# qdr0_1.net
KiCad netlist of a schematic drawn in Altium Designer
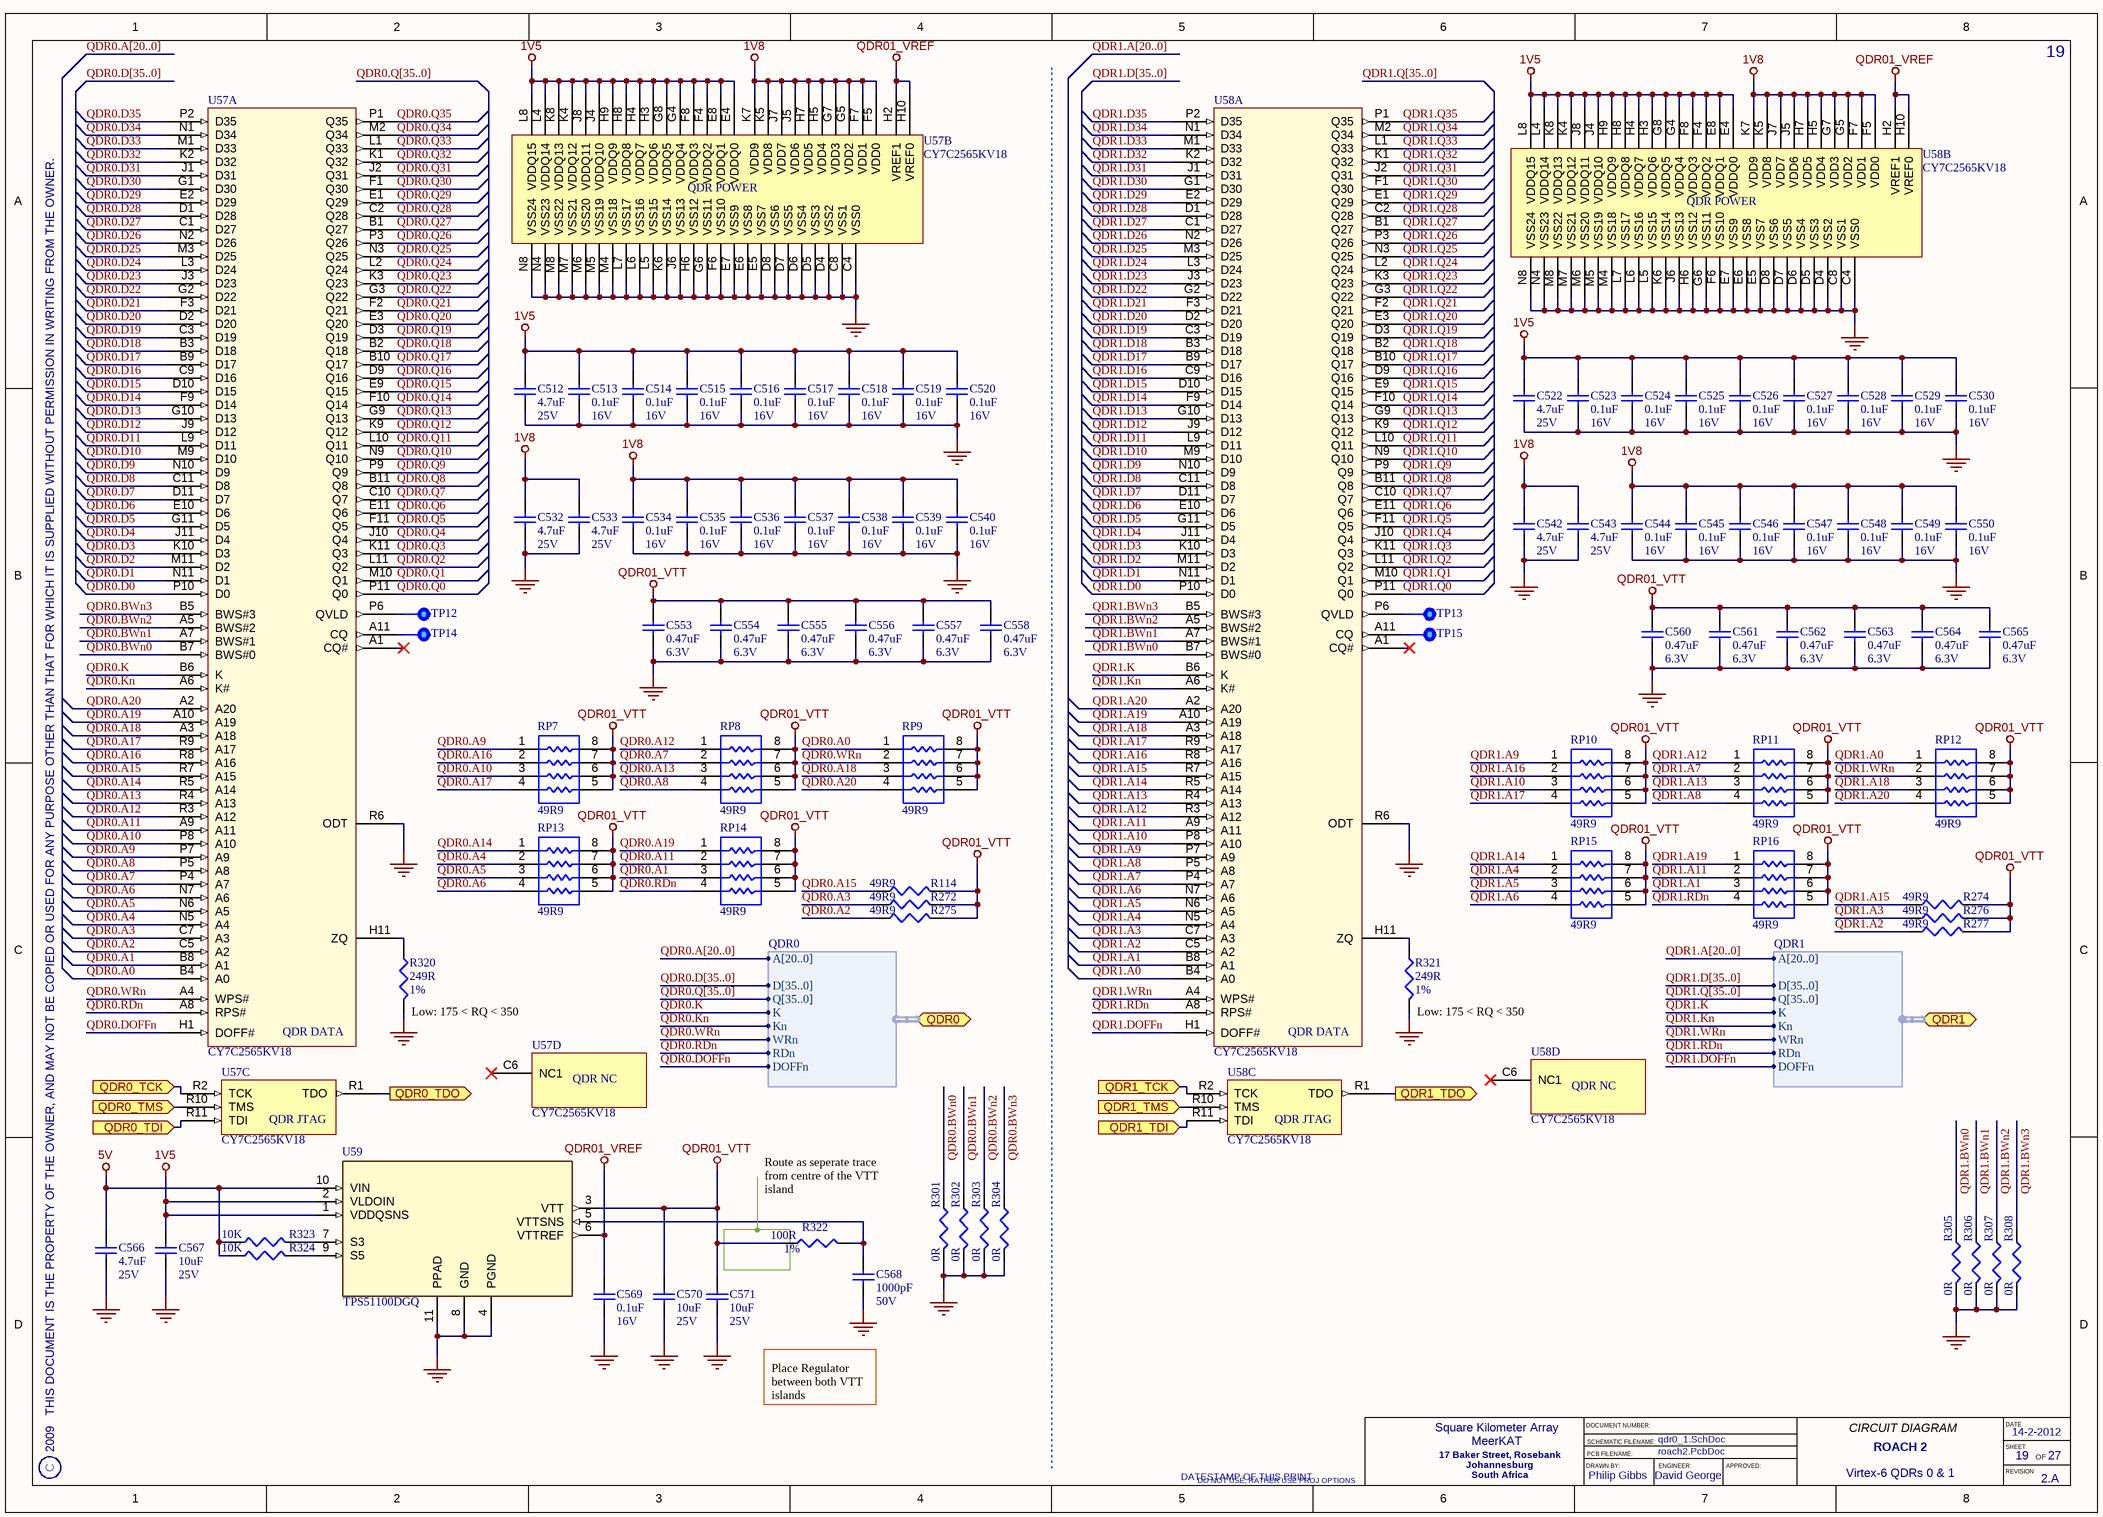
[diagram p0: qdr0_1.SchDoc]

(export (version "E")
  (design (tool "Eeschema 10.0.6"))
  (components
    (comp (ref "C512")
      (value "4.7uF")
      (footprint "CAPC2012X127L")
      (description "4.7uF, Ceramic Capacitor")
      (fields
        (field (name "RATING") "25V")
        (field (name "MANUFACTURER") "MURATA")
        (field (name "PARTNUM") "GRM21BR61E475KA12K")
      )
      (libsource (lib "altium_db") (part "CapStd"))
    )
    (comp (ref "C513")
      (value "0.1uF")
      (footprint "CAPC1005X60L")
      (description "0.1uF, Ceramic Capacitor")
      (fields
        (field (name "RATING") "16V")
        (field (name "MANUFACTURER") "VENKEL")
        (field (name "PARTNUM") "C0402X7R160-104KN")
      )
      (libsource (lib "altium_db") (part "CapStd"))
    )
    (comp (ref "C514")
      (value "0.1uF")
      (footprint "CAPC1005X60L")
      (description "0.1uF, Ceramic Capacitor")
      (fields
        (field (name "RATING") "16V")
        (field (name "MANUFACTURER") "VENKEL")
        (field (name "PARTNUM") "C0402X7R160-104KN")
      )
      (libsource (lib "altium_db") (part "CapStd"))
    )
    (comp (ref "C515")
      (value "0.1uF")
      (footprint "CAPC1005X60L")
      (description "0.1uF, Ceramic Capacitor")
      (fields
        (field (name "RATING") "16V")
        (field (name "MANUFACTURER") "VENKEL")
        (field (name "PARTNUM") "C0402X7R160-104KN")
      )
      (libsource (lib "altium_db") (part "CapStd"))
    )
    (comp (ref "C516")
      (value "0.1uF")
      (footprint "CAPC1005X60L")
      (description "0.1uF, Ceramic Capacitor")
      (fields
        (field (name "RATING") "16V")
        (field (name "MANUFACTURER") "VENKEL")
        (field (name "PARTNUM") "C0402X7R160-104KN")
      )
      (libsource (lib "altium_db") (part "CapStd"))
    )
    (comp (ref "C517")
      (value "0.1uF")
      (footprint "CAPC1005X60L")
      (description "0.1uF, Ceramic Capacitor")
      (fields
        (field (name "RATING") "16V")
        (field (name "MANUFACTURER") "VENKEL")
        (field (name "PARTNUM") "C0402X7R160-104KN")
      )
      (libsource (lib "altium_db") (part "CapStd"))
    )
    (comp (ref "C518")
      (value "0.1uF")
      (footprint "CAPC1005X60L")
      (description "0.1uF, Ceramic Capacitor")
      (fields
        (field (name "RATING") "16V")
        (field (name "MANUFACTURER") "VENKEL")
        (field (name "PARTNUM") "C0402X7R160-104KN")
      )
      (libsource (lib "altium_db") (part "CapStd"))
    )
    (comp (ref "C519")
      (value "0.1uF")
      (footprint "CAPC1005X60L")
      (description "0.1uF, Ceramic Capacitor")
      (fields
        (field (name "RATING") "16V")
        (field (name "MANUFACTURER") "VENKEL")
        (field (name "PARTNUM") "C0402X7R160-104KN")
      )
      (libsource (lib "altium_db") (part "CapStd"))
    )
    (comp (ref "C520")
      (value "0.1uF")
      (footprint "CAPC1005X60L")
      (description "0.1uF, Ceramic Capacitor")
      (fields
        (field (name "RATING") "16V")
        (field (name "MANUFACTURER") "VENKEL")
        (field (name "PARTNUM") "C0402X7R160-104KN")
      )
      (libsource (lib "altium_db") (part "CapStd"))
    )
    (comp (ref "C522")
      (value "4.7uF")
      (footprint "CAPC2012X127L")
      (description "4.7uF, Ceramic Capacitor")
      (fields
        (field (name "RATING") "25V")
        (field (name "MANUFACTURER") "MURATA")
        (field (name "PARTNUM") "GRM21BR61E475KA12K")
      )
      (libsource (lib "altium_db") (part "CapStd"))
    )
    (comp (ref "C523")
      (value "0.1uF")
      (footprint "CAPC1005X60L")
      (description "0.1uF, Ceramic Capacitor")
      (fields
        (field (name "RATING") "16V")
        (field (name "MANUFACTURER") "VENKEL")
        (field (name "PARTNUM") "C0402X7R160-104KN")
      )
      (libsource (lib "altium_db") (part "CapStd"))
    )
    (comp (ref "C524")
      (value "0.1uF")
      (footprint "CAPC1005X60L")
      (description "0.1uF, Ceramic Capacitor")
      (fields
        (field (name "RATING") "16V")
        (field (name "MANUFACTURER") "VENKEL")
        (field (name "PARTNUM") "C0402X7R160-104KN")
      )
      (libsource (lib "altium_db") (part "CapStd"))
    )
    (comp (ref "C525")
      (value "0.1uF")
      (footprint "CAPC1005X60L")
      (description "0.1uF, Ceramic Capacitor")
      (fields
        (field (name "RATING") "16V")
        (field (name "MANUFACTURER") "VENKEL")
        (field (name "PARTNUM") "C0402X7R160-104KN")
      )
      (libsource (lib "altium_db") (part "CapStd"))
    )
    (comp (ref "C526")
      (value "0.1uF")
      (footprint "CAPC1005X60L")
      (description "0.1uF, Ceramic Capacitor")
      (fields
        (field (name "RATING") "16V")
        (field (name "MANUFACTURER") "VENKEL")
        (field (name "PARTNUM") "C0402X7R160-104KN")
      )
      (libsource (lib "altium_db") (part "CapStd"))
    )
    (comp (ref "C527")
      (value "0.1uF")
      (footprint "CAPC1005X60L")
      (description "0.1uF, Ceramic Capacitor")
      (fields
        (field (name "RATING") "16V")
        (field (name "MANUFACTURER") "VENKEL")
        (field (name "PARTNUM") "C0402X7R160-104KN")
      )
      (libsource (lib "altium_db") (part "CapStd"))
    )
    (comp (ref "C528")
      (value "0.1uF")
      (footprint "CAPC1005X60L")
      (description "0.1uF, Ceramic Capacitor")
      (fields
        (field (name "RATING") "16V")
        (field (name "MANUFACTURER") "VENKEL")
        (field (name "PARTNUM") "C0402X7R160-104KN")
      )
      (libsource (lib "altium_db") (part "CapStd"))
    )
    (comp (ref "C529")
      (value "0.1uF")
      (footprint "CAPC1005X60L")
      (description "0.1uF, Ceramic Capacitor")
      (fields
        (field (name "RATING") "16V")
        (field (name "MANUFACTURER") "VENKEL")
        (field (name "PARTNUM") "C0402X7R160-104KN")
      )
      (libsource (lib "altium_db") (part "CapStd"))
    )
    (comp (ref "C530")
      (value "0.1uF")
      (footprint "CAPC1005X60L")
      (description "0.1uF, Ceramic Capacitor")
      (fields
        (field (name "RATING") "16V")
        (field (name "MANUFACTURER") "VENKEL")
        (field (name "PARTNUM") "C0402X7R160-104KN")
      )
      (libsource (lib "altium_db") (part "CapStd"))
    )
    (comp (ref "C532")
      (value "4.7uF")
      (footprint "CAPC2012X127L")
      (description "4.7uF, Ceramic Capacitor")
      (fields
        (field (name "RATING") "25V")
        (field (name "MANUFACTURER") "MURATA")
        (field (name "PARTNUM") "GRM21BR61E475KA12K")
      )
      (libsource (lib "altium_db") (part "CapStd"))
    )
    (comp (ref "C533")
      (value "4.7uF")
      (footprint "CAPC2012X127L")
      (description "4.7uF, Ceramic Capacitor")
      (fields
        (field (name "RATING") "25V")
        (field (name "MANUFACTURER") "MURATA")
        (field (name "PARTNUM") "GRM21BR61E475KA12K")
      )
      (libsource (lib "altium_db") (part "CapStd"))
    )
    (comp (ref "C534")
      (value "0.1uF")
      (footprint "CAPC1005X60L")
      (description "0.1uF, Ceramic Capacitor")
      (fields
        (field (name "RATING") "16V")
        (field (name "MANUFACTURER") "VENKEL")
        (field (name "PARTNUM") "C0402X7R160-104KN")
      )
      (libsource (lib "altium_db") (part "CapStd"))
    )
    (comp (ref "C535")
      (value "0.1uF")
      (footprint "CAPC1005X60L")
      (description "0.1uF, Ceramic Capacitor")
      (fields
        (field (name "RATING") "16V")
        (field (name "MANUFACTURER") "VENKEL")
        (field (name "PARTNUM") "C0402X7R160-104KN")
      )
      (libsource (lib "altium_db") (part "CapStd"))
    )
    (comp (ref "C536")
      (value "0.1uF")
      (footprint "CAPC1005X60L")
      (description "0.1uF, Ceramic Capacitor")
      (fields
        (field (name "RATING") "16V")
        (field (name "MANUFACTURER") "VENKEL")
        (field (name "PARTNUM") "C0402X7R160-104KN")
      )
      (libsource (lib "altium_db") (part "CapStd"))
    )
    (comp (ref "C537")
      (value "0.1uF")
      (footprint "CAPC1005X60L")
      (description "0.1uF, Ceramic Capacitor")
      (fields
        (field (name "RATING") "16V")
        (field (name "MANUFACTURER") "VENKEL")
        (field (name "PARTNUM") "C0402X7R160-104KN")
      )
      (libsource (lib "altium_db") (part "CapStd"))
    )
    (comp (ref "C538")
      (value "0.1uF")
      (footprint "CAPC1005X60L")
      (description "0.1uF, Ceramic Capacitor")
      (fields
        (field (name "RATING") "16V")
        (field (name "MANUFACTURER") "VENKEL")
        (field (name "PARTNUM") "C0402X7R160-104KN")
      )
      (libsource (lib "altium_db") (part "CapStd"))
    )
    (comp (ref "C539")
      (value "0.1uF")
      (footprint "CAPC1005X60L")
      (description "0.1uF, Ceramic Capacitor")
      (fields
        (field (name "RATING") "16V")
        (field (name "MANUFACTURER") "VENKEL")
        (field (name "PARTNUM") "C0402X7R160-104KN")
      )
      (libsource (lib "altium_db") (part "CapStd"))
    )
    (comp (ref "C540")
      (value "0.1uF")
      (footprint "CAPC1005X60L")
      (description "0.1uF, Ceramic Capacitor")
      (fields
        (field (name "RATING") "16V")
        (field (name "MANUFACTURER") "VENKEL")
        (field (name "PARTNUM") "C0402X7R160-104KN")
      )
      (libsource (lib "altium_db") (part "CapStd"))
    )
    (comp (ref "C542")
      (value "4.7uF")
      (footprint "CAPC2012X127L")
      (description "4.7uF, Ceramic Capacitor")
      (fields
        (field (name "RATING") "25V")
        (field (name "MANUFACTURER") "MURATA")
        (field (name "PARTNUM") "GRM21BR61E475KA12K")
      )
      (libsource (lib "altium_db") (part "CapStd"))
    )
    (comp (ref "C543")
      (value "4.7uF")
      (footprint "CAPC2012X127L")
      (description "4.7uF, Ceramic Capacitor")
      (fields
        (field (name "RATING") "25V")
        (field (name "MANUFACTURER") "MURATA")
        (field (name "PARTNUM") "GRM21BR61E475KA12K")
      )
      (libsource (lib "altium_db") (part "CapStd"))
    )
    (comp (ref "C544")
      (value "0.1uF")
      (footprint "CAPC1005X60L")
      (description "0.1uF, Ceramic Capacitor")
      (fields
        (field (name "RATING") "16V")
        (field (name "MANUFACTURER") "VENKEL")
        (field (name "PARTNUM") "C0402X7R160-104KN")
      )
      (libsource (lib "altium_db") (part "CapStd"))
    )
    (comp (ref "C545")
      (value "0.1uF")
      (footprint "CAPC1005X60L")
      (description "0.1uF, Ceramic Capacitor")
      (fields
        (field (name "RATING") "16V")
        (field (name "MANUFACTURER") "VENKEL")
        (field (name "PARTNUM") "C0402X7R160-104KN")
      )
      (libsource (lib "altium_db") (part "CapStd"))
    )
    (comp (ref "C546")
      (value "0.1uF")
      (footprint "CAPC1005X60L")
      (description "0.1uF, Ceramic Capacitor")
      (fields
        (field (name "RATING") "16V")
        (field (name "MANUFACTURER") "VENKEL")
        (field (name "PARTNUM") "C0402X7R160-104KN")
      )
      (libsource (lib "altium_db") (part "CapStd"))
    )
    (comp (ref "C547")
      (value "0.1uF")
      (footprint "CAPC1005X60L")
      (description "0.1uF, Ceramic Capacitor")
      (fields
        (field (name "RATING") "16V")
        (field (name "MANUFACTURER") "VENKEL")
        (field (name "PARTNUM") "C0402X7R160-104KN")
      )
      (libsource (lib "altium_db") (part "CapStd"))
    )
    (comp (ref "C548")
      (value "0.1uF")
      (footprint "CAPC1005X60L")
      (description "0.1uF, Ceramic Capacitor")
      (fields
        (field (name "RATING") "16V")
        (field (name "MANUFACTURER") "VENKEL")
        (field (name "PARTNUM") "C0402X7R160-104KN")
      )
      (libsource (lib "altium_db") (part "CapStd"))
    )
    (comp (ref "C549")
      (value "0.1uF")
      (footprint "CAPC1005X60L")
      (description "0.1uF, Ceramic Capacitor")
      (fields
        (field (name "RATING") "16V")
        (field (name "MANUFACTURER") "VENKEL")
        (field (name "PARTNUM") "C0402X7R160-104KN")
      )
      (libsource (lib "altium_db") (part "CapStd"))
    )
    (comp (ref "C550")
      (value "0.1uF")
      (footprint "CAPC1005X60L")
      (description "0.1uF, Ceramic Capacitor")
      (fields
        (field (name "RATING") "16V")
        (field (name "MANUFACTURER") "VENKEL")
        (field (name "PARTNUM") "C0402X7R160-104KN")
      )
      (libsource (lib "altium_db") (part "CapStd"))
    )
    (comp (ref "C553")
      (value "0.47uF")
      (footprint "CAPC1005X55L")
      (description "0.47uF, Ceramic Capacitor")
      (fields
        (field (name "RATING") "6.3V")
        (field (name "MANUFACTURER") "MURATA")
        (field (name "PARTNUM") "GRM155R60J474KE19")
      )
      (libsource (lib "altium_db") (part "CapStd"))
    )
    (comp (ref "C554")
      (value "0.47uF")
      (footprint "CAPC1005X55L")
      (description "0.47uF, Ceramic Capacitor")
      (fields
        (field (name "RATING") "6.3V")
        (field (name "MANUFACTURER") "MURATA")
        (field (name "PARTNUM") "GRM155R60J474KE19")
      )
      (libsource (lib "altium_db") (part "CapStd"))
    )
    (comp (ref "C555")
      (value "0.47uF")
      (footprint "CAPC1005X55L")
      (description "0.47uF, Ceramic Capacitor")
      (fields
        (field (name "RATING") "6.3V")
        (field (name "MANUFACTURER") "MURATA")
        (field (name "PARTNUM") "GRM155R60J474KE19")
      )
      (libsource (lib "altium_db") (part "CapStd"))
    )
    (comp (ref "C556")
      (value "0.47uF")
      (footprint "CAPC1005X55L")
      (description "0.47uF, Ceramic Capacitor")
      (fields
        (field (name "RATING") "6.3V")
        (field (name "MANUFACTURER") "MURATA")
        (field (name "PARTNUM") "GRM155R60J474KE19")
      )
      (libsource (lib "altium_db") (part "CapStd"))
    )
    (comp (ref "C557")
      (value "0.47uF")
      (footprint "CAPC1005X55L")
      (description "0.47uF, Ceramic Capacitor")
      (fields
        (field (name "RATING") "6.3V")
        (field (name "MANUFACTURER") "MURATA")
        (field (name "PARTNUM") "GRM155R60J474KE19")
      )
      (libsource (lib "altium_db") (part "CapStd"))
    )
    (comp (ref "C558")
      (value "0.47uF")
      (footprint "CAPC1005X55L")
      (description "0.47uF, Ceramic Capacitor")
      (fields
        (field (name "RATING") "6.3V")
        (field (name "MANUFACTURER") "MURATA")
        (field (name "PARTNUM") "GRM155R60J474KE19")
      )
      (libsource (lib "altium_db") (part "CapStd"))
    )
    (comp (ref "C560")
      (value "0.47uF")
      (footprint "CAPC1005X55L")
      (description "0.47uF, Ceramic Capacitor")
      (fields
        (field (name "RATING") "6.3V")
        (field (name "MANUFACTURER") "MURATA")
        (field (name "PARTNUM") "GRM155R60J474KE19")
      )
      (libsource (lib "altium_db") (part "CapStd"))
    )
    (comp (ref "C561")
      (value "0.47uF")
      (footprint "CAPC1005X55L")
      (description "0.47uF, Ceramic Capacitor")
      (fields
        (field (name "RATING") "6.3V")
        (field (name "MANUFACTURER") "MURATA")
        (field (name "PARTNUM") "GRM155R60J474KE19")
      )
      (libsource (lib "altium_db") (part "CapStd"))
    )
    (comp (ref "C562")
      (value "0.47uF")
      (footprint "CAPC1005X55L")
      (description "0.47uF, Ceramic Capacitor")
      (fields
        (field (name "RATING") "6.3V")
        (field (name "MANUFACTURER") "MURATA")
        (field (name "PARTNUM") "GRM155R60J474KE19")
      )
      (libsource (lib "altium_db") (part "CapStd"))
    )
    (comp (ref "C563")
      (value "0.47uF")
      (footprint "CAPC1005X55L")
      (description "0.47uF, Ceramic Capacitor")
      (fields
        (field (name "RATING") "6.3V")
        (field (name "MANUFACTURER") "MURATA")
        (field (name "PARTNUM") "GRM155R60J474KE19")
      )
      (libsource (lib "altium_db") (part "CapStd"))
    )
    (comp (ref "C564")
      (value "0.47uF")
      (footprint "CAPC1005X55L")
      (description "0.47uF, Ceramic Capacitor")
      (fields
        (field (name "RATING") "6.3V")
        (field (name "MANUFACTURER") "MURATA")
        (field (name "PARTNUM") "GRM155R60J474KE19")
      )
      (libsource (lib "altium_db") (part "CapStd"))
    )
    (comp (ref "C565")
      (value "0.47uF")
      (footprint "CAPC1005X55L")
      (description "0.47uF, Ceramic Capacitor")
      (fields
        (field (name "RATING") "6.3V")
        (field (name "MANUFACTURER") "MURATA")
        (field (name "PARTNUM") "GRM155R60J474KE19")
      )
      (libsource (lib "altium_db") (part "CapStd"))
    )
    (comp (ref "C566")
      (value "4.7uF")
      (footprint "CAPC2012X127L")
      (description "4.7uF, Ceramic Capacitor")
      (fields
        (field (name "RATING") "25V")
        (field (name "MANUFACTURER") "MURATA")
        (field (name "PARTNUM") "GRM21BR61E475KA12K")
      )
      (libsource (lib "altium_db") (part "CapStd"))
    )
    (comp (ref "C567")
      (value "10uF")
      (footprint "CAPC3225X200L")
      (description "10uF, Ceramic Capacitor")
      (fields
        (field (name "RATING") "25V")
        (field (name "MANUFACTURER") "MURATA")
        (field (name "PARTNUM") "GRM32DR61E106KA12L")
      )
      (libsource (lib "altium_db") (part "CapStd"))
    )
    (comp (ref "C568")
      (value "1000pF")
      (footprint "CAPC1005X55L")
      (description "1000pF, Ceramic Capacitor")
      (fields
        (field (name "RATING") "50V")
        (field (name "MANUFACTURER") "MURATA")
        (field (name "PARTNUM") "GRM155R61H102KA01D")
      )
      (libsource (lib "altium_db") (part "CapStd"))
    )
    (comp (ref "C569")
      (value "0.1uF")
      (footprint "CAPC1005X60L")
      (description "0.1uF, Ceramic Capacitor")
      (fields
        (field (name "RATING") "16V")
        (field (name "MANUFACTURER") "VENKEL")
        (field (name "PARTNUM") "C0402X7R160-104KN")
      )
      (libsource (lib "altium_db") (part "CapStd"))
    )
    (comp (ref "C570")
      (value "10uF")
      (footprint "CAPC3225X200L")
      (description "10uF, Ceramic Capacitor")
      (fields
        (field (name "RATING") "25V")
        (field (name "MANUFACTURER") "MURATA")
        (field (name "PARTNUM") "GRM32DR61E106KA12L")
      )
      (libsource (lib "altium_db") (part "CapStd"))
    )
    (comp (ref "C571")
      (value "10uF")
      (footprint "CAPC3225X200L")
      (description "10uF, Ceramic Capacitor")
      (fields
        (field (name "RATING") "25V")
        (field (name "MANUFACTURER") "MURATA")
        (field (name "PARTNUM") "GRM32DR61E106KA12L")
      )
      (libsource (lib "altium_db") (part "CapStd"))
    )
    (comp (ref "R114")
      (value "49R9")
      (footprint "RESC1005X40L")
      (description "49R9, 1.1mm x 0.5mm, Thick Film Resistor")
      (fields (field (name "MANUFACTURER") "ROYALOHM") (field (name "PARTNUM") "0402WGF499JT1E"))
      (libsource (lib "altium_db") (part "ResStd"))
    )
    (comp (ref "R272")
      (value "49R9")
      (footprint "RESC1005X40L")
      (description "49R9, 1.1mm x 0.5mm, Thick Film Resistor")
      (fields (field (name "MANUFACTURER") "ROYALOHM") (field (name "PARTNUM") "0402WGF499JT1E"))
      (libsource (lib "altium_db") (part "ResStd"))
    )
    (comp (ref "R274")
      (value "49R9")
      (footprint "RESC1005X40L")
      (description "49R9, 1.1mm x 0.5mm, Thick Film Resistor")
      (fields (field (name "MANUFACTURER") "ROYALOHM") (field (name "PARTNUM") "0402WGF499JT1E"))
      (libsource (lib "altium_db") (part "ResStd"))
    )
    (comp (ref "R275")
      (value "49R9")
      (footprint "RESC1005X40L")
      (description "49R9, 1.1mm x 0.5mm, Thick Film Resistor")
      (fields (field (name "MANUFACTURER") "ROYALOHM") (field (name "PARTNUM") "0402WGF499JT1E"))
      (libsource (lib "altium_db") (part "ResStd"))
    )
    (comp (ref "R276")
      (value "49R9")
      (footprint "RESC1005X40L")
      (description "49R9, 1.1mm x 0.5mm, Thick Film Resistor")
      (fields (field (name "MANUFACTURER") "ROYALOHM") (field (name "PARTNUM") "0402WGF499JT1E"))
      (libsource (lib "altium_db") (part "ResStd"))
    )
    (comp (ref "R277")
      (value "49R9")
      (footprint "RESC1005X40L")
      (description "49R9, 1.1mm x 0.5mm, Thick Film Resistor")
      (fields (field (name "MANUFACTURER") "ROYALOHM") (field (name "PARTNUM") "0402WGF499JT1E"))
      (libsource (lib "altium_db") (part "ResStd"))
    )
    (comp (ref "R301")
      (value "0R")
      (footprint "RESC1005X40L")
      (description "0R, 1.1mm x 0.5mm, Thick Film Resistor")
      (fields (field (name "MANUFACTURER") "ROYALOHM") (field (name "PARTNUM") "0402WG00000T1E"))
      (libsource (lib "altium_db") (part "ResStd"))
    )
    (comp (ref "R302")
      (value "0R")
      (footprint "RESC1005X40L")
      (description "0R, 1.1mm x 0.5mm, Thick Film Resistor")
      (fields (field (name "MANUFACTURER") "ROYALOHM") (field (name "PARTNUM") "0402WG00000T1E"))
      (libsource (lib "altium_db") (part "ResStd"))
    )
    (comp (ref "R303")
      (value "0R")
      (footprint "RESC1005X40L")
      (description "0R, 1.1mm x 0.5mm, Thick Film Resistor")
      (fields (field (name "MANUFACTURER") "ROYALOHM") (field (name "PARTNUM") "0402WG00000T1E"))
      (libsource (lib "altium_db") (part "ResStd"))
    )
    (comp (ref "R304")
      (value "0R")
      (footprint "RESC1005X40L")
      (description "0R, 1.1mm x 0.5mm, Thick Film Resistor")
      (fields (field (name "MANUFACTURER") "ROYALOHM") (field (name "PARTNUM") "0402WG00000T1E"))
      (libsource (lib "altium_db") (part "ResStd"))
    )
    (comp (ref "R305")
      (value "0R")
      (footprint "RESC1005X40L")
      (description "0R, 1.1mm x 0.5mm, Thick Film Resistor")
      (fields (field (name "MANUFACTURER") "ROYALOHM") (field (name "PARTNUM") "0402WG00000T1E"))
      (libsource (lib "altium_db") (part "ResStd"))
    )
    (comp (ref "R306")
      (value "0R")
      (footprint "RESC1005X40L")
      (description "0R, 1.1mm x 0.5mm, Thick Film Resistor")
      (fields (field (name "MANUFACTURER") "ROYALOHM") (field (name "PARTNUM") "0402WG00000T1E"))
      (libsource (lib "altium_db") (part "ResStd"))
    )
    (comp (ref "R307")
      (value "0R")
      (footprint "RESC1005X40L")
      (description "0R, 1.1mm x 0.5mm, Thick Film Resistor")
      (fields (field (name "MANUFACTURER") "ROYALOHM") (field (name "PARTNUM") "0402WG00000T1E"))
      (libsource (lib "altium_db") (part "ResStd"))
    )
    (comp (ref "R308")
      (value "0R")
      (footprint "RESC1005X40L")
      (description "0R, 1.1mm x 0.5mm, Thick Film Resistor")
      (fields (field (name "MANUFACTURER") "ROYALOHM") (field (name "PARTNUM") "0402WG00000T1E"))
      (libsource (lib "altium_db") (part "ResStd"))
    )
    (comp (ref "R320")
      (value "249R")
      (footprint "RESC1005X40L")
      (description "249R, 1.1mm x 0.5mm, Thick Film Resistor")
      (fields
        (field (name "MANUFACTURER") "ROYALOHM")
        (field (name "PARTNUM") "0402WGF2490T1E")
        (field (name "TOLERANCE") "1%")
      )
      (libsource (lib "altium_db") (part "ResStd"))
    )
    (comp (ref "R321")
      (value "249R")
      (footprint "RESC1005X40L")
      (description "249R, 1.1mm x 0.5mm, Thick Film Resistor")
      (fields
        (field (name "MANUFACTURER") "ROYALOHM")
        (field (name "PARTNUM") "0402WGF2490T1E")
        (field (name "TOLERANCE") "1%")
      )
      (libsource (lib "altium_db") (part "ResStd"))
    )
    (comp (ref "R322")
      (value "100R")
      (footprint "RESC1005X40L")
      (description "100R, 1.1mm x 0.5mm, Thick Film Resistor")
      (fields
        (field (name "MANUFACTURER") "ROYALOHM")
        (field (name "PARTNUM") "0402WGF0101T1E")
        (field (name "TOLERANCE") "1%")
      )
      (libsource (lib "altium_db") (part "ResStd"))
    )
    (comp (ref "R323")
      (value "10K")
      (footprint "RESC1005X40L")
      (description "10K, 1.1mm x 0.5mm, Thick Film Resistor")
      (fields (field (name "MANUFACTURER") "ROYALOHM") (field (name "PARTNUM") "0402WGJ0103T1E"))
      (libsource (lib "altium_db") (part "ResStd"))
    )
    (comp (ref "R324")
      (value "10K")
      (footprint "RESC1005X40L")
      (description "10K, 1.1mm x 0.5mm, Thick Film Resistor")
      (fields (field (name "MANUFACTURER") "ROYALOHM") (field (name "PARTNUM") "0402WGJ0103T1E"))
      (libsource (lib "altium_db") (part "ResStd"))
    )
    (comp (ref "RP7")
      (value "49R9")
      (footprint "RESCAV50P100X200X45-8L")
      (description "4-Wide, Isolated, Thick Film Resistor Network")
      (fields (field (name "MANUFACTURER") "ROYALOHM") (field (name "PARTNUM") "4D02WGJ0510B1E"))
      (libsource (lib "altium_db") (part "ResPack4"))
    )
    (comp (ref "RP8")
      (value "49R9")
      (footprint "RESCAV50P100X200X45-8L")
      (description "4-Wide, Isolated, Thick Film Resistor Network")
      (fields (field (name "MANUFACTURER") "ROYALOHM") (field (name "PARTNUM") "4D02WGJ0510B1E"))
      (libsource (lib "altium_db") (part "ResPack4"))
    )
    (comp (ref "RP9")
      (value "49R9")
      (footprint "RESCAV50P100X200X45-8L")
      (description "4-Wide, Isolated, Thick Film Resistor Network")
      (fields (field (name "MANUFACTURER") "ROYALOHM") (field (name "PARTNUM") "4D02WGJ0510B1E"))
      (libsource (lib "altium_db") (part "ResPack4"))
    )
    (comp (ref "RP10")
      (value "49R9")
      (footprint "RESCAV50P100X200X45-8L")
      (description "4-Wide, Isolated, Thick Film Resistor Network")
      (fields (field (name "MANUFACTURER") "ROYALOHM") (field (name "PARTNUM") "4D02WGJ0510B1E"))
      (libsource (lib "altium_db") (part "ResPack4"))
    )
    (comp (ref "RP11")
      (value "49R9")
      (footprint "RESCAV50P100X200X45-8L")
      (description "4-Wide, Isolated, Thick Film Resistor Network")
      (fields (field (name "MANUFACTURER") "ROYALOHM") (field (name "PARTNUM") "4D02WGJ0510B1E"))
      (libsource (lib "altium_db") (part "ResPack4"))
    )
    (comp (ref "RP12")
      (value "49R9")
      (footprint "RESCAV50P100X200X45-8L")
      (description "4-Wide, Isolated, Thick Film Resistor Network")
      (fields (field (name "MANUFACTURER") "ROYALOHM") (field (name "PARTNUM") "4D02WGJ0510B1E"))
      (libsource (lib "altium_db") (part "ResPack4"))
    )
    (comp (ref "RP13")
      (value "49R9")
      (footprint "RESCAV50P100X200X45-8L")
      (description "4-Wide, Isolated, Thick Film Resistor Network")
      (fields (field (name "MANUFACTURER") "ROYALOHM") (field (name "PARTNUM") "4D02WGJ0510B1E"))
      (libsource (lib "altium_db") (part "ResPack4"))
    )
    (comp (ref "RP14")
      (value "49R9")
      (footprint "RESCAV50P100X200X45-8L")
      (description "4-Wide, Isolated, Thick Film Resistor Network")
      (fields (field (name "MANUFACTURER") "ROYALOHM") (field (name "PARTNUM") "4D02WGJ0510B1E"))
      (libsource (lib "altium_db") (part "ResPack4"))
    )
    (comp (ref "RP15")
      (value "49R9")
      (footprint "RESCAV50P100X200X45-8L")
      (description "4-Wide, Isolated, Thick Film Resistor Network")
      (fields (field (name "MANUFACTURER") "ROYALOHM") (field (name "PARTNUM") "4D02WGJ0510B1E"))
      (libsource (lib "altium_db") (part "ResPack4"))
    )
    (comp (ref "RP16")
      (value "49R9")
      (footprint "RESCAV50P100X200X45-8L")
      (description "4-Wide, Isolated, Thick Film Resistor Network")
      (fields (field (name "MANUFACTURER") "ROYALOHM") (field (name "PARTNUM") "4D02WGJ0510B1E"))
      (libsource (lib "altium_db") (part "ResPack4"))
    )
    (comp (ref "TP12")
      (value "Testpoint")
      (footprint "TP100")
      (description "1mm Diameter, through-hole, Circular Test-point")
      (libsource (lib "altium_db") (part "Testpoint"))
    )
    (comp (ref "TP13")
      (value "Testpoint")
      (footprint "TP100")
      (description "1mm Diameter, through-hole, Circular Test-point")
      (libsource (lib "altium_db") (part "Testpoint"))
    )
    (comp (ref "TP14")
      (value "Testpoint")
      (footprint "TP100")
      (description "1mm Diameter, through-hole, Circular Test-point")
      (libsource (lib "altium_db") (part "Testpoint"))
    )
    (comp (ref "TP15")
      (value "Testpoint")
      (footprint "TP100")
      (description "1mm Diameter, through-hole, Circular Test-point")
      (libsource (lib "altium_db") (part "Testpoint"))
    )
    (comp (ref "U57")
      (value "CY7C2565KV18")
      (footprint "FBGA_165-Ball")
      (description "72Mb, 36-Bit wide, QDR2+ Synchronous SRAM with ODT")
      (fields (field (name "MANUFACTURER") "Cypress") (field (name "PARTNUM") "CY7C2565KV18-450BZXC"))
      (libsource (lib "altium_db") (part "QDR2PLUS_36BIT"))
    )
    (comp (ref "U58")
      (value "CY7C2565KV18")
      (footprint "FBGA_165-Ball")
      (description "72Mb, 36-Bit wide, QDR2+ Synchronous SRAM with ODT")
      (fields (field (name "MANUFACTURER") "Cypress") (field (name "PARTNUM") "CY7C2565KV18-450BZXC"))
      (libsource (lib "altium_db") (part "QDR2PLUS_36BIT"))
    )
    (comp (ref "U59")
      (value "TPS51100DGQ")
      (footprint "MSOP_10-N")
      (description "3A Sink/Source Regulator")
      (fields (field (name "MANUFACTURER") "Texas Instruments"))
      (libsource (lib "altium_db") (part "TPS51100DGQ"))
    )
  )
  (nets
    (net (code "3") (name "/QDR0.A0") (class "Default")
      (node (ref "RP9") (pin "1") (pinfunction "1_1") (pintype "passive"))
      (node (ref "U57") (pin "B4") (pinfunction "A0_B4") (pintype "input"))
    )
    (net (code "4") (name "/QDR0.A1") (class "Default")
      (node (ref "RP14") (pin "3") (pinfunction "3_3") (pintype "passive"))
      (node (ref "U57") (pin "B8") (pinfunction "A1_B8") (pintype "input"))
    )
    (net (code "5") (name "/QDR0.A2") (class "Default")
      (node (ref "R275") (pin "1") (pinfunction "1_1") (pintype "passive"))
      (node (ref "U57") (pin "C5") (pinfunction "A2_C5") (pintype "input"))
    )
    (net (code "6") (name "/QDR0.A3") (class "Default")
      (node (ref "R272") (pin "1") (pinfunction "1_1") (pintype "passive"))
      (node (ref "U57") (pin "C7") (pinfunction "A3_C7") (pintype "input"))
    )
    (net (code "7") (name "/QDR0.A4") (class "Default")
      (node (ref "RP13") (pin "2") (pinfunction "2_2") (pintype "passive"))
      (node (ref "U57") (pin "N5") (pinfunction "A4_N5") (pintype "input"))
    )
    (net (code "8") (name "/QDR0.A5") (class "Default")
      (node (ref "RP13") (pin "3") (pinfunction "3_3") (pintype "passive"))
      (node (ref "U57") (pin "N6") (pinfunction "A5_N6") (pintype "input"))
    )
    (net (code "9") (name "/QDR0.A6") (class "Default")
      (node (ref "RP13") (pin "4") (pinfunction "4_4") (pintype "passive"))
      (node (ref "U57") (pin "N7") (pinfunction "A6_N7") (pintype "input"))
    )
    (net (code "10") (name "/QDR0.A7") (class "Default")
      (node (ref "RP8") (pin "2") (pinfunction "2_2") (pintype "passive"))
      (node (ref "U57") (pin "P4") (pinfunction "A7_P4") (pintype "input"))
    )
    (net (code "11") (name "/QDR0.A8") (class "Default")
      (node (ref "RP8") (pin "4") (pinfunction "4_4") (pintype "passive"))
      (node (ref "U57") (pin "P5") (pinfunction "A8_P5") (pintype "input"))
    )
    (net (code "12") (name "/QDR0.A9") (class "Default")
      (node (ref "RP7") (pin "1") (pinfunction "1_1") (pintype "passive"))
      (node (ref "U57") (pin "P7") (pinfunction "A9_P7") (pintype "input"))
    )
    (net (code "13") (name "/QDR0.A10") (class "Default")
      (node (ref "RP7") (pin "3") (pinfunction "3_3") (pintype "passive"))
      (node (ref "U57") (pin "P8") (pinfunction "A10_P8") (pintype "input"))
    )
    (net (code "14") (name "/QDR0.A11") (class "Default")
      (node (ref "RP14") (pin "2") (pinfunction "2_2") (pintype "passive"))
      (node (ref "U57") (pin "A9") (pinfunction "A11_A9") (pintype "input"))
    )
    (net (code "15") (name "/QDR0.A12") (class "Default")
      (node (ref "RP8") (pin "1") (pinfunction "1_1") (pintype "passive"))
      (node (ref "U57") (pin "R3") (pinfunction "A12_R3") (pintype "input"))
    )
    (net (code "16") (name "/QDR0.A13") (class "Default")
      (node (ref "RP8") (pin "3") (pinfunction "3_3") (pintype "passive"))
      (node (ref "U57") (pin "R4") (pinfunction "A13_R4") (pintype "input"))
    )
    (net (code "17") (name "/QDR0.A14") (class "Default")
      (node (ref "RP13") (pin "1") (pinfunction "1_1") (pintype "passive"))
      (node (ref "U57") (pin "R5") (pinfunction "A14_R5") (pintype "input"))
    )
    (net (code "18") (name "/QDR0.A15") (class "Default")
      (node (ref "R114") (pin "1") (pinfunction "1_1") (pintype "passive"))
      (node (ref "U57") (pin "R7") (pinfunction "A15_R7") (pintype "input"))
    )
    (net (code "19") (name "/QDR0.A16") (class "Default")
      (node (ref "RP7") (pin "2") (pinfunction "2_2") (pintype "passive"))
      (node (ref "U57") (pin "R8") (pinfunction "A16_R8") (pintype "input"))
    )
    (net (code "20") (name "/QDR0.A17") (class "Default")
      (node (ref "RP7") (pin "4") (pinfunction "4_4") (pintype "passive"))
      (node (ref "U57") (pin "R9") (pinfunction "A17_R9") (pintype "input"))
    )
    (net (code "21") (name "/QDR0.A18") (class "Default")
      (node (ref "RP9") (pin "3") (pinfunction "3_3") (pintype "passive"))
      (node (ref "U57") (pin "A3") (pinfunction "A18_A3") (pintype "input"))
    )
    (net (code "22") (name "/QDR0.A19") (class "Default")
      (node (ref "RP14") (pin "1") (pinfunction "1_1") (pintype "passive"))
      (node (ref "U57") (pin "A10") (pinfunction "A19_A10") (pintype "input"))
    )
    (net (code "23") (name "/QDR0.A20") (class "Default")
      (node (ref "RP9") (pin "4") (pinfunction "4_4") (pintype "passive"))
      (node (ref "U57") (pin "A2") (pinfunction "A20_A2") (pintype "input"))
    )
    (net (code "25") (name "/QDR0.BWn0") (class "Default")
      (node (ref "R301") (pin "1") (pinfunction "1_1") (pintype "passive"))
      (node (ref "U57") (pin "B7") (pinfunction "BWS#0_B7") (pintype "input"))
    )
    (net (code "26") (name "/QDR0.BWn1") (class "Default")
      (node (ref "R302") (pin "1") (pinfunction "1_1") (pintype "passive"))
      (node (ref "U57") (pin "A7") (pinfunction "BWS#1_A7") (pintype "input"))
    )
    (net (code "27") (name "/QDR0.BWn2") (class "Default")
      (node (ref "R303") (pin "1") (pinfunction "1_1") (pintype "passive"))
      (node (ref "U57") (pin "A5") (pinfunction "BWS#2_A5") (pintype "input"))
    )
    (net (code "28") (name "/QDR0.BWn3") (class "Default")
      (node (ref "R304") (pin "1") (pinfunction "1_1") (pintype "passive"))
      (node (ref "U57") (pin "B5") (pinfunction "BWS#3_B5") (pintype "input"))
    )
    (net (code "29") (name "/QDR0.D0") (class "Default")
      (node (ref "U57") (pin "P10") (pinfunction "D0_P10") (pintype "input"))
    )
    (net (code "30") (name "/QDR0.D1") (class "Default")
      (node (ref "U57") (pin "N11") (pinfunction "D1_N11") (pintype "input"))
    )
    (net (code "31") (name "/QDR0.D2") (class "Default")
      (node (ref "U57") (pin "M11") (pinfunction "D2_M11") (pintype "input"))
    )
    (net (code "32") (name "/QDR0.D3") (class "Default")
      (node (ref "U57") (pin "K10") (pinfunction "D3_K10") (pintype "input"))
    )
    (net (code "33") (name "/QDR0.D4") (class "Default")
      (node (ref "U57") (pin "J11") (pinfunction "D4_J11") (pintype "input"))
    )
    (net (code "34") (name "/QDR0.D5") (class "Default")
      (node (ref "U57") (pin "G11") (pinfunction "D5_G11") (pintype "input"))
    )
    (net (code "35") (name "/QDR0.D6") (class "Default")
      (node (ref "U57") (pin "E10") (pinfunction "D6_E10") (pintype "input"))
    )
    (net (code "36") (name "/QDR0.D7") (class "Default")
      (node (ref "U57") (pin "D11") (pinfunction "D7_D11") (pintype "input"))
    )
    (net (code "37") (name "/QDR0.D8") (class "Default")
      (node (ref "U57") (pin "C11") (pinfunction "D8_C11") (pintype "input"))
    )
    (net (code "38") (name "/QDR0.D9") (class "Default")
      (node (ref "U57") (pin "N10") (pinfunction "D9_N10") (pintype "input"))
    )
    (net (code "39") (name "/QDR0.D10") (class "Default")
      (node (ref "U57") (pin "M9") (pinfunction "D10_M9") (pintype "input"))
    )
    (net (code "40") (name "/QDR0.D11") (class "Default")
      (node (ref "U57") (pin "L9") (pinfunction "D11_L9") (pintype "input"))
    )
    (net (code "41") (name "/QDR0.D12") (class "Default")
      (node (ref "U57") (pin "J9") (pinfunction "D12_J9") (pintype "input"))
    )
    (net (code "42") (name "/QDR0.D13") (class "Default")
      (node (ref "U57") (pin "G10") (pinfunction "D13_G10") (pintype "input"))
    )
    (net (code "43") (name "/QDR0.D14") (class "Default")
      (node (ref "U57") (pin "F9") (pinfunction "D14_F9") (pintype "input"))
    )
    (net (code "44") (name "/QDR0.D15") (class "Default")
      (node (ref "U57") (pin "D10") (pinfunction "D15_D10") (pintype "input"))
    )
    (net (code "45") (name "/QDR0.D16") (class "Default")
      (node (ref "U57") (pin "C9") (pinfunction "D16_C9") (pintype "input"))
    )
    (net (code "46") (name "/QDR0.D17") (class "Default")
      (node (ref "U57") (pin "B9") (pinfunction "D17_B9") (pintype "input"))
    )
    (net (code "47") (name "/QDR0.D18") (class "Default")
      (node (ref "U57") (pin "B3") (pinfunction "D18_B3") (pintype "input"))
    )
    (net (code "48") (name "/QDR0.D19") (class "Default")
      (node (ref "U57") (pin "C3") (pinfunction "D19_C3") (pintype "input"))
    )
    (net (code "49") (name "/QDR0.D20") (class "Default")
      (node (ref "U57") (pin "D2") (pinfunction "D20_D2") (pintype "input"))
    )
    (net (code "50") (name "/QDR0.D21") (class "Default")
      (node (ref "U57") (pin "F3") (pinfunction "D21_F3") (pintype "input"))
    )
    (net (code "51") (name "/QDR0.D22") (class "Default")
      (node (ref "U57") (pin "G2") (pinfunction "D22_G2") (pintype "input"))
    )
    (net (code "52") (name "/QDR0.D23") (class "Default")
      (node (ref "U57") (pin "J3") (pinfunction "D23_J3") (pintype "input"))
    )
    (net (code "53") (name "/QDR0.D24") (class "Default")
      (node (ref "U57") (pin "L3") (pinfunction "D24_L3") (pintype "input"))
    )
    (net (code "54") (name "/QDR0.D25") (class "Default")
      (node (ref "U57") (pin "M3") (pinfunction "D25_M3") (pintype "input"))
    )
    (net (code "55") (name "/QDR0.D26") (class "Default")
      (node (ref "U57") (pin "N2") (pinfunction "D26_N2") (pintype "input"))
    )
    (net (code "56") (name "/QDR0.D27") (class "Default")
      (node (ref "U57") (pin "C1") (pinfunction "D27_C1") (pintype "input"))
    )
    (net (code "57") (name "/QDR0.D28") (class "Default")
      (node (ref "U57") (pin "D1") (pinfunction "D28_D1") (pintype "input"))
    )
    (net (code "58") (name "/QDR0.D29") (class "Default")
      (node (ref "U57") (pin "E2") (pinfunction "D29_E2") (pintype "input"))
    )
    (net (code "59") (name "/QDR0.D30") (class "Default")
      (node (ref "U57") (pin "G1") (pinfunction "D30_G1") (pintype "input"))
    )
    (net (code "60") (name "/QDR0.D31") (class "Default")
      (node (ref "U57") (pin "J1") (pinfunction "D31_J1") (pintype "input"))
    )
    (net (code "61") (name "/QDR0.D32") (class "Default")
      (node (ref "U57") (pin "K2") (pinfunction "D32_K2") (pintype "input"))
    )
    (net (code "62") (name "/QDR0.D33") (class "Default")
      (node (ref "U57") (pin "M1") (pinfunction "D33_M1") (pintype "input"))
    )
    (net (code "63") (name "/QDR0.D34") (class "Default")
      (node (ref "U57") (pin "N1") (pinfunction "D34_N1") (pintype "input"))
    )
    (net (code "64") (name "/QDR0.D35") (class "Default")
      (node (ref "U57") (pin "P2") (pinfunction "D35_P2") (pintype "input"))
    )
    (net (code "65") (name "/QDR0.DOFFn") (class "Default")
      (node (ref "U57") (pin "H1") (pinfunction "DOFF#_H1") (pintype "input"))
    )
    (net (code "67") (name "/QDR0.K") (class "Default")
      (node (ref "U57") (pin "B6") (pinfunction "K_B6") (pintype "input"))
    )
    (net (code "68") (name "/QDR0.Kn") (class "Default")
      (node (ref "U57") (pin "A6") (pinfunction "K#_A6") (pintype "input"))
    )
    (net (code "69") (name "/QDR0.Q0") (class "Default")
      (node (ref "U57") (pin "P11") (pinfunction "Q0_P11") (pintype "output"))
    )
    (net (code "70") (name "/QDR0.Q1") (class "Default")
      (node (ref "U57") (pin "M10") (pinfunction "Q1_M10") (pintype "output"))
    )
    (net (code "71") (name "/QDR0.Q2") (class "Default")
      (node (ref "U57") (pin "L11") (pinfunction "Q2_L11") (pintype "output"))
    )
    (net (code "72") (name "/QDR0.Q3") (class "Default")
      (node (ref "U57") (pin "K11") (pinfunction "Q3_K11") (pintype "output"))
    )
    (net (code "73") (name "/QDR0.Q4") (class "Default")
      (node (ref "U57") (pin "J10") (pinfunction "Q4_J10") (pintype "output"))
    )
    (net (code "74") (name "/QDR0.Q5") (class "Default")
      (node (ref "U57") (pin "F11") (pinfunction "Q5_F11") (pintype "output"))
    )
    (net (code "75") (name "/QDR0.Q6") (class "Default")
      (node (ref "U57") (pin "E11") (pinfunction "Q6_E11") (pintype "output"))
    )
    (net (code "76") (name "/QDR0.Q7") (class "Default")
      (node (ref "U57") (pin "C10") (pinfunction "Q7_C10") (pintype "output"))
    )
    (net (code "77") (name "/QDR0.Q8") (class "Default")
      (node (ref "U57") (pin "B11") (pinfunction "Q8_B11") (pintype "output"))
    )
    (net (code "78") (name "/QDR0.Q9") (class "Default")
      (node (ref "U57") (pin "P9") (pinfunction "Q9_P9") (pintype "output"))
    )
    (net (code "79") (name "/QDR0.Q10") (class "Default")
      (node (ref "U57") (pin "N9") (pinfunction "Q10_N9") (pintype "output"))
    )
    (net (code "80") (name "/QDR0.Q11") (class "Default")
      (node (ref "U57") (pin "L10") (pinfunction "Q11_L10") (pintype "output"))
    )
    (net (code "81") (name "/QDR0.Q12") (class "Default")
      (node (ref "U57") (pin "K9") (pinfunction "Q12_K9") (pintype "output"))
    )
    (net (code "82") (name "/QDR0.Q13") (class "Default")
      (node (ref "U57") (pin "G9") (pinfunction "Q13_G9") (pintype "output"))
    )
    (net (code "83") (name "/QDR0.Q14") (class "Default")
      (node (ref "U57") (pin "F10") (pinfunction "Q14_F10") (pintype "output"))
    )
    (net (code "84") (name "/QDR0.Q15") (class "Default")
      (node (ref "U57") (pin "E9") (pinfunction "Q15_E9") (pintype "output"))
    )
    (net (code "85") (name "/QDR0.Q16") (class "Default")
      (node (ref "U57") (pin "D9") (pinfunction "Q16_D9") (pintype "output"))
    )
    (net (code "86") (name "/QDR0.Q17") (class "Default")
      (node (ref "U57") (pin "B10") (pinfunction "Q17_B10") (pintype "output"))
    )
    (net (code "87") (name "/QDR0.Q18") (class "Default")
      (node (ref "U57") (pin "B2") (pinfunction "Q18_B2") (pintype "output"))
    )
    (net (code "88") (name "/QDR0.Q19") (class "Default")
      (node (ref "U57") (pin "D3") (pinfunction "Q19_D3") (pintype "output"))
    )
    (net (code "89") (name "/QDR0.Q20") (class "Default")
      (node (ref "U57") (pin "E3") (pinfunction "Q20_E3") (pintype "output"))
    )
    (net (code "90") (name "/QDR0.Q21") (class "Default")
      (node (ref "U57") (pin "F2") (pinfunction "Q21_F2") (pintype "output"))
    )
    (net (code "91") (name "/QDR0.Q22") (class "Default")
      (node (ref "U57") (pin "G3") (pinfunction "Q22_G3") (pintype "output"))
    )
    (net (code "92") (name "/QDR0.Q23") (class "Default")
      (node (ref "U57") (pin "K3") (pinfunction "Q23_K3") (pintype "output"))
    )
    (net (code "93") (name "/QDR0.Q24") (class "Default")
      (node (ref "U57") (pin "L2") (pinfunction "Q24_L2") (pintype "output"))
    )
    (net (code "94") (name "/QDR0.Q25") (class "Default")
      (node (ref "U57") (pin "N3") (pinfunction "Q25_N3") (pintype "output"))
    )
    (net (code "95") (name "/QDR0.Q26") (class "Default")
      (node (ref "U57") (pin "P3") (pinfunction "Q26_P3") (pintype "output"))
    )
    (net (code "96") (name "/QDR0.Q27") (class "Default")
      (node (ref "U57") (pin "B1") (pinfunction "Q27_B1") (pintype "output"))
    )
    (net (code "97") (name "/QDR0.Q28") (class "Default")
      (node (ref "U57") (pin "C2") (pinfunction "Q28_C2") (pintype "output"))
    )
    (net (code "98") (name "/QDR0.Q29") (class "Default")
      (node (ref "U57") (pin "E1") (pinfunction "Q29_E1") (pintype "output"))
    )
    (net (code "99") (name "/QDR0.Q30") (class "Default")
      (node (ref "U57") (pin "F1") (pinfunction "Q30_F1") (pintype "output"))
    )
    (net (code "100") (name "/QDR0.Q31") (class "Default")
      (node (ref "U57") (pin "J2") (pinfunction "Q31_J2") (pintype "output"))
    )
    (net (code "101") (name "/QDR0.Q32") (class "Default")
      (node (ref "U57") (pin "K1") (pinfunction "Q32_K1") (pintype "output"))
    )
    (net (code "102") (name "/QDR0.Q33") (class "Default")
      (node (ref "U57") (pin "L1") (pinfunction "Q33_L1") (pintype "output"))
    )
    (net (code "103") (name "/QDR0.Q34") (class "Default")
      (node (ref "U57") (pin "M2") (pinfunction "Q34_M2") (pintype "output"))
    )
    (net (code "104") (name "/QDR0.Q35") (class "Default")
      (node (ref "U57") (pin "P1") (pinfunction "Q35_P1") (pintype "output"))
    )
    (net (code "106") (name "/QDR0.RDn") (class "Default")
      (node (ref "RP14") (pin "4") (pinfunction "4_4") (pintype "passive"))
      (node (ref "U57") (pin "A8") (pinfunction "RPS#_A8") (pintype "input"))
    )
    (net (code "107") (name "/QDR0.WRn") (class "Default")
      (node (ref "RP9") (pin "2") (pinfunction "2_2") (pintype "passive"))
      (node (ref "U57") (pin "A4") (pinfunction "WPS#_A4") (pintype "input"))
    )
    (net (code "108") (name "/QDR0_TCK") (class "Default")
      (node (ref "U57") (pin "R2") (pinfunction "TCK_R2") (pintype "input"))
    )
    (net (code "109") (name "/QDR0_TDI") (class "Default")
      (node (ref "U57") (pin "R11") (pinfunction "TDI_R11") (pintype "input"))
    )
    (net (code "110") (name "/QDR0_TDO") (class "Default")
      (node (ref "U57") (pin "R1") (pinfunction "TDO_R1") (pintype "output"))
    )
    (net (code "111") (name "/QDR0_TMS") (class "Default")
      (node (ref "U57") (pin "R10") (pinfunction "TMS_R10") (pintype "input"))
    )
    (net (code "112") (name "/QDR1.A0") (class "Default")
      (node (ref "RP12") (pin "1") (pinfunction "1_1") (pintype "passive"))
      (node (ref "U58") (pin "B4") (pinfunction "A0_B4") (pintype "input"))
    )
    (net (code "113") (name "/QDR1.A1") (class "Default")
      (node (ref "RP16") (pin "3") (pinfunction "3_3") (pintype "passive"))
      (node (ref "U58") (pin "B8") (pinfunction "A1_B8") (pintype "input"))
    )
    (net (code "114") (name "/QDR1.A2") (class "Default")
      (node (ref "R277") (pin "1") (pinfunction "1_1") (pintype "passive"))
      (node (ref "U58") (pin "C5") (pinfunction "A2_C5") (pintype "input"))
    )
    (net (code "115") (name "/QDR1.A3") (class "Default")
      (node (ref "R276") (pin "1") (pinfunction "1_1") (pintype "passive"))
      (node (ref "U58") (pin "C7") (pinfunction "A3_C7") (pintype "input"))
    )
    (net (code "116") (name "/QDR1.A4") (class "Default")
      (node (ref "RP15") (pin "2") (pinfunction "2_2") (pintype "passive"))
      (node (ref "U58") (pin "N5") (pinfunction "A4_N5") (pintype "input"))
    )
    (net (code "117") (name "/QDR1.A5") (class "Default")
      (node (ref "RP15") (pin "3") (pinfunction "3_3") (pintype "passive"))
      (node (ref "U58") (pin "N6") (pinfunction "A5_N6") (pintype "input"))
    )
    (net (code "118") (name "/QDR1.A6") (class "Default")
      (node (ref "RP15") (pin "4") (pinfunction "4_4") (pintype "passive"))
      (node (ref "U58") (pin "N7") (pinfunction "A6_N7") (pintype "input"))
    )
    (net (code "119") (name "/QDR1.A7") (class "Default")
      (node (ref "RP11") (pin "2") (pinfunction "2_2") (pintype "passive"))
      (node (ref "U58") (pin "P4") (pinfunction "A7_P4") (pintype "input"))
    )
    (net (code "120") (name "/QDR1.A8") (class "Default")
      (node (ref "RP11") (pin "4") (pinfunction "4_4") (pintype "passive"))
      (node (ref "U58") (pin "P5") (pinfunction "A8_P5") (pintype "input"))
    )
    (net (code "121") (name "/QDR1.A9") (class "Default")
      (node (ref "RP10") (pin "1") (pinfunction "1_1") (pintype "passive"))
      (node (ref "U58") (pin "P7") (pinfunction "A9_P7") (pintype "input"))
    )
    (net (code "122") (name "/QDR1.A10") (class "Default")
      (node (ref "RP10") (pin "3") (pinfunction "3_3") (pintype "passive"))
      (node (ref "U58") (pin "P8") (pinfunction "A10_P8") (pintype "input"))
    )
    (net (code "123") (name "/QDR1.A11") (class "Default")
      (node (ref "RP16") (pin "2") (pinfunction "2_2") (pintype "passive"))
      (node (ref "U58") (pin "A9") (pinfunction "A11_A9") (pintype "input"))
    )
    (net (code "124") (name "/QDR1.A12") (class "Default")
      (node (ref "RP11") (pin "1") (pinfunction "1_1") (pintype "passive"))
      (node (ref "U58") (pin "R3") (pinfunction "A12_R3") (pintype "input"))
    )
    (net (code "125") (name "/QDR1.A13") (class "Default")
      (node (ref "RP11") (pin "3") (pinfunction "3_3") (pintype "passive"))
      (node (ref "U58") (pin "R4") (pinfunction "A13_R4") (pintype "input"))
    )
    (net (code "126") (name "/QDR1.A14") (class "Default")
      (node (ref "RP15") (pin "1") (pinfunction "1_1") (pintype "passive"))
      (node (ref "U58") (pin "R5") (pinfunction "A14_R5") (pintype "input"))
    )
    (net (code "127") (name "/QDR1.A15") (class "Default")
      (node (ref "R274") (pin "1") (pinfunction "1_1") (pintype "passive"))
      (node (ref "U58") (pin "R7") (pinfunction "A15_R7") (pintype "input"))
    )
    (net (code "128") (name "/QDR1.A16") (class "Default")
      (node (ref "RP10") (pin "2") (pinfunction "2_2") (pintype "passive"))
      (node (ref "U58") (pin "R8") (pinfunction "A16_R8") (pintype "input"))
    )
    (net (code "129") (name "/QDR1.A17") (class "Default")
      (node (ref "RP10") (pin "4") (pinfunction "4_4") (pintype "passive"))
      (node (ref "U58") (pin "R9") (pinfunction "A17_R9") (pintype "input"))
    )
    (net (code "130") (name "/QDR1.A18") (class "Default")
      (node (ref "RP12") (pin "3") (pinfunction "3_3") (pintype "passive"))
      (node (ref "U58") (pin "A3") (pinfunction "A18_A3") (pintype "input"))
    )
    (net (code "131") (name "/QDR1.A19") (class "Default")
      (node (ref "RP16") (pin "1") (pinfunction "1_1") (pintype "passive"))
      (node (ref "U58") (pin "A10") (pinfunction "A19_A10") (pintype "input"))
    )
    (net (code "132") (name "/QDR1.A20") (class "Default")
      (node (ref "RP12") (pin "4") (pinfunction "4_4") (pintype "passive"))
      (node (ref "U58") (pin "A2") (pinfunction "A20_A2") (pintype "input"))
    )
    (net (code "134") (name "/QDR1.BWn0") (class "Default")
      (node (ref "R305") (pin "1") (pinfunction "1_1") (pintype "passive"))
      (node (ref "U58") (pin "B7") (pinfunction "BWS#0_B7") (pintype "input"))
    )
    (net (code "135") (name "/QDR1.BWn1") (class "Default")
      (node (ref "R306") (pin "1") (pinfunction "1_1") (pintype "passive"))
      (node (ref "U58") (pin "A7") (pinfunction "BWS#1_A7") (pintype "input"))
    )
    (net (code "136") (name "/QDR1.BWn2") (class "Default")
      (node (ref "R307") (pin "1") (pinfunction "1_1") (pintype "passive"))
      (node (ref "U58") (pin "A5") (pinfunction "BWS#2_A5") (pintype "input"))
    )
    (net (code "137") (name "/QDR1.BWn3") (class "Default")
      (node (ref "R308") (pin "1") (pinfunction "1_1") (pintype "passive"))
      (node (ref "U58") (pin "B5") (pinfunction "BWS#3_B5") (pintype "input"))
    )
    (net (code "138") (name "/QDR1.D0") (class "Default")
      (node (ref "U58") (pin "P10") (pinfunction "D0_P10") (pintype "input"))
    )
    (net (code "139") (name "/QDR1.D1") (class "Default")
      (node (ref "U58") (pin "N11") (pinfunction "D1_N11") (pintype "input"))
    )
    (net (code "140") (name "/QDR1.D2") (class "Default")
      (node (ref "U58") (pin "M11") (pinfunction "D2_M11") (pintype "input"))
    )
    (net (code "141") (name "/QDR1.D3") (class "Default")
      (node (ref "U58") (pin "K10") (pinfunction "D3_K10") (pintype "input"))
    )
    (net (code "142") (name "/QDR1.D4") (class "Default")
      (node (ref "U58") (pin "J11") (pinfunction "D4_J11") (pintype "input"))
    )
    (net (code "143") (name "/QDR1.D5") (class "Default")
      (node (ref "U58") (pin "G11") (pinfunction "D5_G11") (pintype "input"))
    )
    (net (code "144") (name "/QDR1.D6") (class "Default")
      (node (ref "U58") (pin "E10") (pinfunction "D6_E10") (pintype "input"))
    )
    (net (code "145") (name "/QDR1.D7") (class "Default")
      (node (ref "U58") (pin "D11") (pinfunction "D7_D11") (pintype "input"))
    )
    (net (code "146") (name "/QDR1.D8") (class "Default")
      (node (ref "U58") (pin "C11") (pinfunction "D8_C11") (pintype "input"))
    )
    (net (code "147") (name "/QDR1.D9") (class "Default")
      (node (ref "U58") (pin "N10") (pinfunction "D9_N10") (pintype "input"))
    )
    (net (code "148") (name "/QDR1.D10") (class "Default")
      (node (ref "U58") (pin "M9") (pinfunction "D10_M9") (pintype "input"))
    )
    (net (code "149") (name "/QDR1.D11") (class "Default")
      (node (ref "U58") (pin "L9") (pinfunction "D11_L9") (pintype "input"))
    )
    (net (code "150") (name "/QDR1.D12") (class "Default")
      (node (ref "U58") (pin "J9") (pinfunction "D12_J9") (pintype "input"))
    )
    (net (code "151") (name "/QDR1.D13") (class "Default")
      (node (ref "U58") (pin "G10") (pinfunction "D13_G10") (pintype "input"))
    )
    (net (code "152") (name "/QDR1.D14") (class "Default")
      (node (ref "U58") (pin "F9") (pinfunction "D14_F9") (pintype "input"))
    )
    (net (code "153") (name "/QDR1.D15") (class "Default")
      (node (ref "U58") (pin "D10") (pinfunction "D15_D10") (pintype "input"))
    )
    (net (code "154") (name "/QDR1.D16") (class "Default")
      (node (ref "U58") (pin "C9") (pinfunction "D16_C9") (pintype "input"))
    )
    (net (code "155") (name "/QDR1.D17") (class "Default")
      (node (ref "U58") (pin "B9") (pinfunction "D17_B9") (pintype "input"))
    )
    (net (code "156") (name "/QDR1.D18") (class "Default")
      (node (ref "U58") (pin "B3") (pinfunction "D18_B3") (pintype "input"))
    )
    (net (code "157") (name "/QDR1.D19") (class "Default")
      (node (ref "U58") (pin "C3") (pinfunction "D19_C3") (pintype "input"))
    )
    (net (code "158") (name "/QDR1.D20") (class "Default")
      (node (ref "U58") (pin "D2") (pinfunction "D20_D2") (pintype "input"))
    )
    (net (code "159") (name "/QDR1.D21") (class "Default")
      (node (ref "U58") (pin "F3") (pinfunction "D21_F3") (pintype "input"))
    )
    (net (code "160") (name "/QDR1.D22") (class "Default")
      (node (ref "U58") (pin "G2") (pinfunction "D22_G2") (pintype "input"))
    )
    (net (code "161") (name "/QDR1.D23") (class "Default")
      (node (ref "U58") (pin "J3") (pinfunction "D23_J3") (pintype "input"))
    )
    (net (code "162") (name "/QDR1.D24") (class "Default")
      (node (ref "U58") (pin "L3") (pinfunction "D24_L3") (pintype "input"))
    )
    (net (code "163") (name "/QDR1.D25") (class "Default")
      (node (ref "U58") (pin "M3") (pinfunction "D25_M3") (pintype "input"))
    )
    (net (code "164") (name "/QDR1.D26") (class "Default")
      (node (ref "U58") (pin "N2") (pinfunction "D26_N2") (pintype "input"))
    )
    (net (code "165") (name "/QDR1.D27") (class "Default")
      (node (ref "U58") (pin "C1") (pinfunction "D27_C1") (pintype "input"))
    )
    (net (code "166") (name "/QDR1.D28") (class "Default")
      (node (ref "U58") (pin "D1") (pinfunction "D28_D1") (pintype "input"))
    )
    (net (code "167") (name "/QDR1.D29") (class "Default")
      (node (ref "U58") (pin "E2") (pinfunction "D29_E2") (pintype "input"))
    )
    (net (code "168") (name "/QDR1.D30") (class "Default")
      (node (ref "U58") (pin "G1") (pinfunction "D30_G1") (pintype "input"))
    )
    (net (code "169") (name "/QDR1.D31") (class "Default")
      (node (ref "U58") (pin "J1") (pinfunction "D31_J1") (pintype "input"))
    )
    (net (code "170") (name "/QDR1.D32") (class "Default")
      (node (ref "U58") (pin "K2") (pinfunction "D32_K2") (pintype "input"))
    )
    (net (code "171") (name "/QDR1.D33") (class "Default")
      (node (ref "U58") (pin "M1") (pinfunction "D33_M1") (pintype "input"))
    )
    (net (code "172") (name "/QDR1.D34") (class "Default")
      (node (ref "U58") (pin "N1") (pinfunction "D34_N1") (pintype "input"))
    )
    (net (code "173") (name "/QDR1.D35") (class "Default")
      (node (ref "U58") (pin "P2") (pinfunction "D35_P2") (pintype "input"))
    )
    (net (code "174") (name "/QDR1.DOFFn") (class "Default")
      (node (ref "U58") (pin "H1") (pinfunction "DOFF#_H1") (pintype "input"))
    )
    (net (code "176") (name "/QDR1.K") (class "Default")
      (node (ref "U58") (pin "B6") (pinfunction "K_B6") (pintype "input"))
    )
    (net (code "177") (name "/QDR1.Kn") (class "Default")
      (node (ref "U58") (pin "A6") (pinfunction "K#_A6") (pintype "input"))
    )
    (net (code "178") (name "/QDR1.Q0") (class "Default")
      (node (ref "U58") (pin "P11") (pinfunction "Q0_P11") (pintype "output"))
    )
    (net (code "179") (name "/QDR1.Q1") (class "Default")
      (node (ref "U58") (pin "M10") (pinfunction "Q1_M10") (pintype "output"))
    )
    (net (code "180") (name "/QDR1.Q2") (class "Default")
      (node (ref "U58") (pin "L11") (pinfunction "Q2_L11") (pintype "output"))
    )
    (net (code "181") (name "/QDR1.Q3") (class "Default")
      (node (ref "U58") (pin "K11") (pinfunction "Q3_K11") (pintype "output"))
    )
    (net (code "182") (name "/QDR1.Q4") (class "Default")
      (node (ref "U58") (pin "J10") (pinfunction "Q4_J10") (pintype "output"))
    )
    (net (code "183") (name "/QDR1.Q5") (class "Default")
      (node (ref "U58") (pin "F11") (pinfunction "Q5_F11") (pintype "output"))
    )
    (net (code "184") (name "/QDR1.Q6") (class "Default")
      (node (ref "U58") (pin "E11") (pinfunction "Q6_E11") (pintype "output"))
    )
    (net (code "185") (name "/QDR1.Q7") (class "Default")
      (node (ref "U58") (pin "C10") (pinfunction "Q7_C10") (pintype "output"))
    )
    (net (code "186") (name "/QDR1.Q8") (class "Default")
      (node (ref "U58") (pin "B11") (pinfunction "Q8_B11") (pintype "output"))
    )
    (net (code "187") (name "/QDR1.Q9") (class "Default")
      (node (ref "U58") (pin "P9") (pinfunction "Q9_P9") (pintype "output"))
    )
    (net (code "188") (name "/QDR1.Q10") (class "Default")
      (node (ref "U58") (pin "N9") (pinfunction "Q10_N9") (pintype "output"))
    )
    (net (code "189") (name "/QDR1.Q11") (class "Default")
      (node (ref "U58") (pin "L10") (pinfunction "Q11_L10") (pintype "output"))
    )
    (net (code "190") (name "/QDR1.Q12") (class "Default")
      (node (ref "U58") (pin "K9") (pinfunction "Q12_K9") (pintype "output"))
    )
    (net (code "191") (name "/QDR1.Q13") (class "Default")
      (node (ref "U58") (pin "G9") (pinfunction "Q13_G9") (pintype "output"))
    )
    (net (code "192") (name "/QDR1.Q14") (class "Default")
      (node (ref "U58") (pin "F10") (pinfunction "Q14_F10") (pintype "output"))
    )
    (net (code "193") (name "/QDR1.Q15") (class "Default")
      (node (ref "U58") (pin "E9") (pinfunction "Q15_E9") (pintype "output"))
    )
    (net (code "194") (name "/QDR1.Q16") (class "Default")
      (node (ref "U58") (pin "D9") (pinfunction "Q16_D9") (pintype "output"))
    )
    (net (code "195") (name "/QDR1.Q17") (class "Default")
      (node (ref "U58") (pin "B10") (pinfunction "Q17_B10") (pintype "output"))
    )
    (net (code "196") (name "/QDR1.Q18") (class "Default")
      (node (ref "U58") (pin "B2") (pinfunction "Q18_B2") (pintype "output"))
    )
    (net (code "197") (name "/QDR1.Q19") (class "Default")
      (node (ref "U58") (pin "D3") (pinfunction "Q19_D3") (pintype "output"))
    )
    (net (code "198") (name "/QDR1.Q20") (class "Default")
      (node (ref "U58") (pin "E3") (pinfunction "Q20_E3") (pintype "output"))
    )
    (net (code "199") (name "/QDR1.Q21") (class "Default")
      (node (ref "U58") (pin "F2") (pinfunction "Q21_F2") (pintype "output"))
    )
    (net (code "200") (name "/QDR1.Q22") (class "Default")
      (node (ref "U58") (pin "G3") (pinfunction "Q22_G3") (pintype "output"))
    )
    (net (code "201") (name "/QDR1.Q23") (class "Default")
      (node (ref "U58") (pin "K3") (pinfunction "Q23_K3") (pintype "output"))
    )
    (net (code "202") (name "/QDR1.Q24") (class "Default")
      (node (ref "U58") (pin "L2") (pinfunction "Q24_L2") (pintype "output"))
    )
    (net (code "203") (name "/QDR1.Q25") (class "Default")
      (node (ref "U58") (pin "N3") (pinfunction "Q25_N3") (pintype "output"))
    )
    (net (code "204") (name "/QDR1.Q26") (class "Default")
      (node (ref "U58") (pin "P3") (pinfunction "Q26_P3") (pintype "output"))
    )
    (net (code "205") (name "/QDR1.Q27") (class "Default")
      (node (ref "U58") (pin "B1") (pinfunction "Q27_B1") (pintype "output"))
    )
    (net (code "206") (name "/QDR1.Q28") (class "Default")
      (node (ref "U58") (pin "C2") (pinfunction "Q28_C2") (pintype "output"))
    )
    (net (code "207") (name "/QDR1.Q29") (class "Default")
      (node (ref "U58") (pin "E1") (pinfunction "Q29_E1") (pintype "output"))
    )
    (net (code "208") (name "/QDR1.Q30") (class "Default")
      (node (ref "U58") (pin "F1") (pinfunction "Q30_F1") (pintype "output"))
    )
    (net (code "209") (name "/QDR1.Q31") (class "Default")
      (node (ref "U58") (pin "J2") (pinfunction "Q31_J2") (pintype "output"))
    )
    (net (code "210") (name "/QDR1.Q32") (class "Default")
      (node (ref "U58") (pin "K1") (pinfunction "Q32_K1") (pintype "output"))
    )
    (net (code "211") (name "/QDR1.Q33") (class "Default")
      (node (ref "U58") (pin "L1") (pinfunction "Q33_L1") (pintype "output"))
    )
    (net (code "212") (name "/QDR1.Q34") (class "Default")
      (node (ref "U58") (pin "M2") (pinfunction "Q34_M2") (pintype "output"))
    )
    (net (code "213") (name "/QDR1.Q35") (class "Default")
      (node (ref "U58") (pin "P1") (pinfunction "Q35_P1") (pintype "output"))
    )
    (net (code "215") (name "/QDR1.RDn") (class "Default")
      (node (ref "RP16") (pin "4") (pinfunction "4_4") (pintype "passive"))
      (node (ref "U58") (pin "A8") (pinfunction "RPS#_A8") (pintype "input"))
    )
    (net (code "216") (name "/QDR1.WRn") (class "Default")
      (node (ref "RP12") (pin "2") (pinfunction "2_2") (pintype "passive"))
      (node (ref "U58") (pin "A4") (pinfunction "WPS#_A4") (pintype "input"))
    )
    (net (code "217") (name "/QDR1_TCK") (class "Default")
      (node (ref "U58") (pin "R2") (pinfunction "TCK_R2") (pintype "input"))
    )
    (net (code "218") (name "/QDR1_TDI") (class "Default")
      (node (ref "U58") (pin "R11") (pinfunction "TDI_R11") (pintype "input"))
    )
    (net (code "219") (name "/QDR1_TDO") (class "Default")
      (node (ref "U58") (pin "R1") (pinfunction "TDO_R1") (pintype "output"))
    )
    (net (code "220") (name "/QDR1_TMS") (class "Default")
      (node (ref "U58") (pin "R10") (pinfunction "TMS_R10") (pintype "input"))
    )
    (net (code "224") (name "1V5") (class "Default")
      (node (ref "C512") (pin "2") (pinfunction "2_2") (pintype "passive"))
      (node (ref "C513") (pin "2") (pinfunction "2_2") (pintype "passive"))
      (node (ref "C514") (pin "2") (pinfunction "2_2") (pintype "passive"))
      (node (ref "C515") (pin "2") (pinfunction "2_2") (pintype "passive"))
      (node (ref "C516") (pin "2") (pinfunction "2_2") (pintype "passive"))
      (node (ref "C517") (pin "2") (pinfunction "2_2") (pintype "passive"))
      (node (ref "C518") (pin "2") (pinfunction "2_2") (pintype "passive"))
      (node (ref "C519") (pin "2") (pinfunction "2_2") (pintype "passive"))
      (node (ref "C520") (pin "2") (pinfunction "2_2") (pintype "passive"))
      (node (ref "C522") (pin "2") (pinfunction "2_2") (pintype "passive"))
      (node (ref "C523") (pin "2") (pinfunction "2_2") (pintype "passive"))
      (node (ref "C524") (pin "2") (pinfunction "2_2") (pintype "passive"))
      (node (ref "C525") (pin "2") (pinfunction "2_2") (pintype "passive"))
      (node (ref "C526") (pin "2") (pinfunction "2_2") (pintype "passive"))
      (node (ref "C527") (pin "2") (pinfunction "2_2") (pintype "passive"))
      (node (ref "C528") (pin "2") (pinfunction "2_2") (pintype "passive"))
      (node (ref "C529") (pin "2") (pinfunction "2_2") (pintype "passive"))
      (node (ref "C530") (pin "2") (pinfunction "2_2") (pintype "passive"))
      (node (ref "C567") (pin "2") (pinfunction "2_2") (pintype "passive"))
      (node (ref "U57") (pin "E4") (pinfunction "VDDQ0_E4") (pintype "power_in"))
      (node (ref "U57") (pin "E8") (pinfunction "VDDQ1_E8") (pintype "power_in"))
      (node (ref "U57") (pin "F4") (pinfunction "VDDQ2_F4") (pintype "power_in"))
      (node (ref "U57") (pin "F8") (pinfunction "VDDQ3_F8") (pintype "power_in"))
      (node (ref "U57") (pin "G4") (pinfunction "VDDQ4_G4") (pintype "power_in"))
      (node (ref "U57") (pin "G8") (pinfunction "VDDQ5_G8") (pintype "power_in"))
      (node (ref "U57") (pin "H3") (pinfunction "VDDQ6_H3") (pintype "power_in"))
      (node (ref "U57") (pin "H4") (pinfunction "VDDQ7_H4") (pintype "power_in"))
      (node (ref "U57") (pin "H8") (pinfunction "VDDQ8_H8") (pintype "power_in"))
      (node (ref "U57") (pin "H9") (pinfunction "VDDQ9_H9") (pintype "power_in"))
      (node (ref "U57") (pin "J4") (pinfunction "VDDQ10_J4") (pintype "power_in"))
      (node (ref "U57") (pin "J8") (pinfunction "VDDQ11_J8") (pintype "power_in"))
      (node (ref "U57") (pin "K4") (pinfunction "VDDQ12_K4") (pintype "power_in"))
      (node (ref "U57") (pin "K8") (pinfunction "VDDQ13_K8") (pintype "power_in"))
      (node (ref "U57") (pin "L4") (pinfunction "VDDQ14_L4") (pintype "power_in"))
      (node (ref "U57") (pin "L8") (pinfunction "VDDQ15_L8") (pintype "power_in"))
      (node (ref "U58") (pin "E4") (pinfunction "VDDQ0_E4") (pintype "power_in"))
      (node (ref "U58") (pin "E8") (pinfunction "VDDQ1_E8") (pintype "power_in"))
      (node (ref "U58") (pin "F4") (pinfunction "VDDQ2_F4") (pintype "power_in"))
      (node (ref "U58") (pin "F8") (pinfunction "VDDQ3_F8") (pintype "power_in"))
      (node (ref "U58") (pin "G4") (pinfunction "VDDQ4_G4") (pintype "power_in"))
      (node (ref "U58") (pin "G8") (pinfunction "VDDQ5_G8") (pintype "power_in"))
      (node (ref "U58") (pin "H3") (pinfunction "VDDQ6_H3") (pintype "power_in"))
      (node (ref "U58") (pin "H4") (pinfunction "VDDQ7_H4") (pintype "power_in"))
      (node (ref "U58") (pin "H8") (pinfunction "VDDQ8_H8") (pintype "power_in"))
      (node (ref "U58") (pin "H9") (pinfunction "VDDQ9_H9") (pintype "power_in"))
      (node (ref "U58") (pin "J4") (pinfunction "VDDQ10_J4") (pintype "power_in"))
      (node (ref "U58") (pin "J8") (pinfunction "VDDQ11_J8") (pintype "power_in"))
      (node (ref "U58") (pin "K4") (pinfunction "VDDQ12_K4") (pintype "power_in"))
      (node (ref "U58") (pin "K8") (pinfunction "VDDQ13_K8") (pintype "power_in"))
      (node (ref "U58") (pin "L4") (pinfunction "VDDQ14_L4") (pintype "power_in"))
      (node (ref "U58") (pin "L8") (pinfunction "VDDQ15_L8") (pintype "power_in"))
      (node (ref "U59") (pin "1") (pinfunction "VDDQSNS_1") (pintype "input"))
      (node (ref "U59") (pin "2") (pinfunction "VLDOIN_2") (pintype "input"))
    )
    (net (code "225") (name "1V8") (class "Default")
      (node (ref "C532") (pin "2") (pinfunction "2_2") (pintype "passive"))
      (node (ref "C533") (pin "2") (pinfunction "2_2") (pintype "passive"))
      (node (ref "C534") (pin "2") (pinfunction "2_2") (pintype "passive"))
      (node (ref "C535") (pin "2") (pinfunction "2_2") (pintype "passive"))
      (node (ref "C536") (pin "2") (pinfunction "2_2") (pintype "passive"))
      (node (ref "C537") (pin "2") (pinfunction "2_2") (pintype "passive"))
      (node (ref "C538") (pin "2") (pinfunction "2_2") (pintype "passive"))
      (node (ref "C539") (pin "2") (pinfunction "2_2") (pintype "passive"))
      (node (ref "C540") (pin "2") (pinfunction "2_2") (pintype "passive"))
      (node (ref "C542") (pin "2") (pinfunction "2_2") (pintype "passive"))
      (node (ref "C543") (pin "2") (pinfunction "2_2") (pintype "passive"))
      (node (ref "C544") (pin "2") (pinfunction "2_2") (pintype "passive"))
      (node (ref "C545") (pin "2") (pinfunction "2_2") (pintype "passive"))
      (node (ref "C546") (pin "2") (pinfunction "2_2") (pintype "passive"))
      (node (ref "C547") (pin "2") (pinfunction "2_2") (pintype "passive"))
      (node (ref "C548") (pin "2") (pinfunction "2_2") (pintype "passive"))
      (node (ref "C549") (pin "2") (pinfunction "2_2") (pintype "passive"))
      (node (ref "C550") (pin "2") (pinfunction "2_2") (pintype "passive"))
      (node (ref "U57") (pin "F5") (pinfunction "VDD0_F5") (pintype "power_in"))
      (node (ref "U57") (pin "F7") (pinfunction "VDD1_F7") (pintype "power_in"))
      (node (ref "U57") (pin "G5") (pinfunction "VDD2_G5") (pintype "power_in"))
      (node (ref "U57") (pin "G7") (pinfunction "VDD3_G7") (pintype "power_in"))
      (node (ref "U57") (pin "H5") (pinfunction "VDD4_H5") (pintype "power_in"))
      (node (ref "U57") (pin "H7") (pinfunction "VDD5_H7") (pintype "power_in"))
      (node (ref "U57") (pin "J5") (pinfunction "VDD6_J5") (pintype "power_in"))
      (node (ref "U57") (pin "J7") (pinfunction "VDD7_J7") (pintype "power_in"))
      (node (ref "U57") (pin "K5") (pinfunction "VDD8_K5") (pintype "power_in"))
      (node (ref "U57") (pin "K7") (pinfunction "VDD9_K7") (pintype "power_in"))
      (node (ref "U58") (pin "F5") (pinfunction "VDD0_F5") (pintype "power_in"))
      (node (ref "U58") (pin "F7") (pinfunction "VDD1_F7") (pintype "power_in"))
      (node (ref "U58") (pin "G5") (pinfunction "VDD2_G5") (pintype "power_in"))
      (node (ref "U58") (pin "G7") (pinfunction "VDD3_G7") (pintype "power_in"))
      (node (ref "U58") (pin "H5") (pinfunction "VDD4_H5") (pintype "power_in"))
      (node (ref "U58") (pin "H7") (pinfunction "VDD5_H7") (pintype "power_in"))
      (node (ref "U58") (pin "J5") (pinfunction "VDD6_J5") (pintype "power_in"))
      (node (ref "U58") (pin "J7") (pinfunction "VDD7_J7") (pintype "power_in"))
      (node (ref "U58") (pin "K5") (pinfunction "VDD8_K5") (pintype "power_in"))
      (node (ref "U58") (pin "K7") (pinfunction "VDD9_K7") (pintype "power_in"))
    )
    (net (code "226") (name "5V") (class "Default")
      (node (ref "C566") (pin "2") (pinfunction "2_2") (pintype "passive"))
      (node (ref "R323") (pin "1") (pinfunction "1_1") (pintype "passive"))
      (node (ref "R324") (pin "1") (pinfunction "1_1") (pintype "passive"))
      (node (ref "U59") (pin "10") (pinfunction "VIN_10") (pintype "input"))
    )
    (net (code "227") (name "GND") (class "Default")
      (node (ref "C512") (pin "1") (pinfunction "1_1") (pintype "passive"))
      (node (ref "C513") (pin "1") (pinfunction "1_1") (pintype "passive"))
      (node (ref "C514") (pin "1") (pinfunction "1_1") (pintype "passive"))
      (node (ref "C515") (pin "1") (pinfunction "1_1") (pintype "passive"))
      (node (ref "C516") (pin "1") (pinfunction "1_1") (pintype "passive"))
      (node (ref "C517") (pin "1") (pinfunction "1_1") (pintype "passive"))
      (node (ref "C518") (pin "1") (pinfunction "1_1") (pintype "passive"))
      (node (ref "C519") (pin "1") (pinfunction "1_1") (pintype "passive"))
      (node (ref "C520") (pin "1") (pinfunction "1_1") (pintype "passive"))
      (node (ref "C522") (pin "1") (pinfunction "1_1") (pintype "passive"))
      (node (ref "C523") (pin "1") (pinfunction "1_1") (pintype "passive"))
      (node (ref "C524") (pin "1") (pinfunction "1_1") (pintype "passive"))
      (node (ref "C525") (pin "1") (pinfunction "1_1") (pintype "passive"))
      (node (ref "C526") (pin "1") (pinfunction "1_1") (pintype "passive"))
      (node (ref "C527") (pin "1") (pinfunction "1_1") (pintype "passive"))
      (node (ref "C528") (pin "1") (pinfunction "1_1") (pintype "passive"))
      (node (ref "C529") (pin "1") (pinfunction "1_1") (pintype "passive"))
      (node (ref "C530") (pin "1") (pinfunction "1_1") (pintype "passive"))
      (node (ref "C532") (pin "1") (pinfunction "1_1") (pintype "passive"))
      (node (ref "C533") (pin "1") (pinfunction "1_1") (pintype "passive"))
      (node (ref "C534") (pin "1") (pinfunction "1_1") (pintype "passive"))
      (node (ref "C535") (pin "1") (pinfunction "1_1") (pintype "passive"))
      (node (ref "C536") (pin "1") (pinfunction "1_1") (pintype "passive"))
      (node (ref "C537") (pin "1") (pinfunction "1_1") (pintype "passive"))
      (node (ref "C538") (pin "1") (pinfunction "1_1") (pintype "passive"))
      (node (ref "C539") (pin "1") (pinfunction "1_1") (pintype "passive"))
      (node (ref "C540") (pin "1") (pinfunction "1_1") (pintype "passive"))
      (node (ref "C542") (pin "1") (pinfunction "1_1") (pintype "passive"))
      (node (ref "C543") (pin "1") (pinfunction "1_1") (pintype "passive"))
      (node (ref "C544") (pin "1") (pinfunction "1_1") (pintype "passive"))
      (node (ref "C545") (pin "1") (pinfunction "1_1") (pintype "passive"))
      (node (ref "C546") (pin "1") (pinfunction "1_1") (pintype "passive"))
      (node (ref "C547") (pin "1") (pinfunction "1_1") (pintype "passive"))
      (node (ref "C548") (pin "1") (pinfunction "1_1") (pintype "passive"))
      (node (ref "C549") (pin "1") (pinfunction "1_1") (pintype "passive"))
      (node (ref "C550") (pin "1") (pinfunction "1_1") (pintype "passive"))
      (node (ref "C553") (pin "1") (pinfunction "1_1") (pintype "passive"))
      (node (ref "C554") (pin "1") (pinfunction "1_1") (pintype "passive"))
      (node (ref "C555") (pin "1") (pinfunction "1_1") (pintype "passive"))
      (node (ref "C556") (pin "1") (pinfunction "1_1") (pintype "passive"))
      (node (ref "C557") (pin "1") (pinfunction "1_1") (pintype "passive"))
      (node (ref "C558") (pin "1") (pinfunction "1_1") (pintype "passive"))
      (node (ref "C560") (pin "1") (pinfunction "1_1") (pintype "passive"))
      (node (ref "C561") (pin "1") (pinfunction "1_1") (pintype "passive"))
      (node (ref "C562") (pin "1") (pinfunction "1_1") (pintype "passive"))
      (node (ref "C563") (pin "1") (pinfunction "1_1") (pintype "passive"))
      (node (ref "C564") (pin "1") (pinfunction "1_1") (pintype "passive"))
      (node (ref "C565") (pin "1") (pinfunction "1_1") (pintype "passive"))
      (node (ref "C566") (pin "1") (pinfunction "1_1") (pintype "passive"))
      (node (ref "C567") (pin "1") (pinfunction "1_1") (pintype "passive"))
      (node (ref "C568") (pin "1") (pinfunction "1_1") (pintype "passive"))
      (node (ref "C569") (pin "1") (pinfunction "1_1") (pintype "passive"))
      (node (ref "C570") (pin "1") (pinfunction "1_1") (pintype "passive"))
      (node (ref "C571") (pin "1") (pinfunction "1_1") (pintype "passive"))
      (node (ref "R301") (pin "2") (pinfunction "2_2") (pintype "passive"))
      (node (ref "R302") (pin "2") (pinfunction "2_2") (pintype "passive"))
      (node (ref "R303") (pin "2") (pinfunction "2_2") (pintype "passive"))
      (node (ref "R304") (pin "2") (pinfunction "2_2") (pintype "passive"))
      (node (ref "R305") (pin "2") (pinfunction "2_2") (pintype "passive"))
      (node (ref "R306") (pin "2") (pinfunction "2_2") (pintype "passive"))
      (node (ref "R307") (pin "2") (pinfunction "2_2") (pintype "passive"))
      (node (ref "R308") (pin "2") (pinfunction "2_2") (pintype "passive"))
      (node (ref "R320") (pin "2") (pinfunction "2_2") (pintype "passive"))
      (node (ref "R321") (pin "2") (pinfunction "2_2") (pintype "passive"))
      (node (ref "U57") (pin "C4") (pinfunction "VSS0_C4") (pintype "power_in"))
      (node (ref "U57") (pin "C8") (pinfunction "VSS1_C8") (pintype "power_in"))
      (node (ref "U57") (pin "D4") (pinfunction "VSS2_D4") (pintype "power_in"))
      (node (ref "U57") (pin "D5") (pinfunction "VSS3_D5") (pintype "power_in"))
      (node (ref "U57") (pin "D6") (pinfunction "VSS4_D6") (pintype "power_in"))
      (node (ref "U57") (pin "D7") (pinfunction "VSS5_D7") (pintype "power_in"))
      (node (ref "U57") (pin "D8") (pinfunction "VSS6_D8") (pintype "power_in"))
      (node (ref "U57") (pin "E5") (pinfunction "VSS7_E5") (pintype "power_in"))
      (node (ref "U57") (pin "E6") (pinfunction "VSS8_E6") (pintype "power_in"))
      (node (ref "U57") (pin "E7") (pinfunction "VSS9_E7") (pintype "power_in"))
      (node (ref "U57") (pin "F6") (pinfunction "VSS10_F6") (pintype "power_in"))
      (node (ref "U57") (pin "G6") (pinfunction "VSS11_G6") (pintype "power_in"))
      (node (ref "U57") (pin "H6") (pinfunction "VSS12_H6") (pintype "power_in"))
      (node (ref "U57") (pin "J6") (pinfunction "VSS13_J6") (pintype "power_in"))
      (node (ref "U57") (pin "K6") (pinfunction "VSS14_K6") (pintype "power_in"))
      (node (ref "U57") (pin "L5") (pinfunction "VSS15_L5") (pintype "power_in"))
      (node (ref "U57") (pin "L6") (pinfunction "VSS16_L6") (pintype "power_in"))
      (node (ref "U57") (pin "L7") (pinfunction "VSS17_L7") (pintype "power_in"))
      (node (ref "U57") (pin "M4") (pinfunction "VSS18_M4") (pintype "power_in"))
      (node (ref "U57") (pin "M5") (pinfunction "VSS19_M5") (pintype "power_in"))
      (node (ref "U57") (pin "M6") (pinfunction "VSS20_M6") (pintype "power_in"))
      (node (ref "U57") (pin "M7") (pinfunction "VSS21_M7") (pintype "power_in"))
      (node (ref "U57") (pin "M8") (pinfunction "VSS22_M8") (pintype "power_in"))
      (node (ref "U57") (pin "N4") (pinfunction "VSS23_N4") (pintype "power_in"))
      (node (ref "U57") (pin "N8") (pinfunction "VSS24_N8") (pintype "power_in"))
      (node (ref "U57") (pin "R6") (pinfunction "ODT_R6") (pintype "passive"))
      (node (ref "U58") (pin "C4") (pinfunction "VSS0_C4") (pintype "power_in"))
      (node (ref "U58") (pin "C8") (pinfunction "VSS1_C8") (pintype "power_in"))
      (node (ref "U58") (pin "D4") (pinfunction "VSS2_D4") (pintype "power_in"))
      (node (ref "U58") (pin "D5") (pinfunction "VSS3_D5") (pintype "power_in"))
      (node (ref "U58") (pin "D6") (pinfunction "VSS4_D6") (pintype "power_in"))
      (node (ref "U58") (pin "D7") (pinfunction "VSS5_D7") (pintype "power_in"))
      (node (ref "U58") (pin "D8") (pinfunction "VSS6_D8") (pintype "power_in"))
      (node (ref "U58") (pin "E5") (pinfunction "VSS7_E5") (pintype "power_in"))
      (node (ref "U58") (pin "E6") (pinfunction "VSS8_E6") (pintype "power_in"))
      (node (ref "U58") (pin "E7") (pinfunction "VSS9_E7") (pintype "power_in"))
      (node (ref "U58") (pin "F6") (pinfunction "VSS10_F6") (pintype "power_in"))
      (node (ref "U58") (pin "G6") (pinfunction "VSS11_G6") (pintype "power_in"))
      (node (ref "U58") (pin "H6") (pinfunction "VSS12_H6") (pintype "power_in"))
      (node (ref "U58") (pin "J6") (pinfunction "VSS13_J6") (pintype "power_in"))
      (node (ref "U58") (pin "K6") (pinfunction "VSS14_K6") (pintype "power_in"))
      (node (ref "U58") (pin "L5") (pinfunction "VSS15_L5") (pintype "power_in"))
      (node (ref "U58") (pin "L6") (pinfunction "VSS16_L6") (pintype "power_in"))
      (node (ref "U58") (pin "L7") (pinfunction "VSS17_L7") (pintype "power_in"))
      (node (ref "U58") (pin "M4") (pinfunction "VSS18_M4") (pintype "power_in"))
      (node (ref "U58") (pin "M5") (pinfunction "VSS19_M5") (pintype "power_in"))
      (node (ref "U58") (pin "M6") (pinfunction "VSS20_M6") (pintype "power_in"))
      (node (ref "U58") (pin "M7") (pinfunction "VSS21_M7") (pintype "power_in"))
      (node (ref "U58") (pin "M8") (pinfunction "VSS22_M8") (pintype "power_in"))
      (node (ref "U58") (pin "N4") (pinfunction "VSS23_N4") (pintype "power_in"))
      (node (ref "U58") (pin "N8") (pinfunction "VSS24_N8") (pintype "power_in"))
      (node (ref "U58") (pin "R6") (pinfunction "ODT_R6") (pintype "passive"))
      (node (ref "U59") (pin "11") (pinfunction "PPAD_11") (pintype "passive"))
      (node (ref "U59") (pin "4") (pinfunction "PGND_4") (pintype "passive"))
      (node (ref "U59") (pin "8") (pinfunction "GND_8") (pintype "passive"))
    )
    (net (code "228") (name "Net-(U57A-CQ)") (class "Default")
      (node (ref "TP14") (pin "1") (pinfunction "1_1") (pintype "passive"))
      (node (ref "U57") (pin "A11") (pinfunction "CQ_A11") (pintype "output"))
    )
    (net (code "229") (name "Net-(U57A-QVLD)") (class "Default")
      (node (ref "TP12") (pin "1") (pinfunction "1_1") (pintype "passive"))
      (node (ref "U57") (pin "P6") (pinfunction "QVLD_P6") (pintype "output"))
    )
    (net (code "230") (name "Net-(U57A-ZQ)") (class "Default")
      (node (ref "R320") (pin "1") (pinfunction "1_1") (pintype "passive"))
      (node (ref "U57") (pin "H11") (pinfunction "ZQ_H11") (pintype "passive"))
    )
    (net (code "231") (name "Net-(U58A-CQ)") (class "Default")
      (node (ref "TP15") (pin "1") (pinfunction "1_1") (pintype "passive"))
      (node (ref "U58") (pin "A11") (pinfunction "CQ_A11") (pintype "output"))
    )
    (net (code "232") (name "Net-(U58A-QVLD)") (class "Default")
      (node (ref "TP13") (pin "1") (pinfunction "1_1") (pintype "passive"))
      (node (ref "U58") (pin "P6") (pinfunction "QVLD_P6") (pintype "output"))
    )
    (net (code "233") (name "Net-(U58A-ZQ)") (class "Default")
      (node (ref "R321") (pin "1") (pinfunction "1_1") (pintype "passive"))
      (node (ref "U58") (pin "H11") (pinfunction "ZQ_H11") (pintype "passive"))
    )
    (net (code "234") (name "Net-(U59-S3)") (class "Default")
      (node (ref "R323") (pin "2") (pinfunction "2_2") (pintype "passive"))
      (node (ref "U59") (pin "7") (pinfunction "S3_7") (pintype "input"))
    )
    (net (code "235") (name "Net-(U59-S5)") (class "Default")
      (node (ref "R324") (pin "2") (pinfunction "2_2") (pintype "passive"))
      (node (ref "U59") (pin "9") (pinfunction "S5_9") (pintype "input"))
    )
    (net (code "236") (name "Net-(U59-VTTSNS)") (class "Default")
      (node (ref "C568") (pin "2") (pinfunction "2_2") (pintype "passive"))
      (node (ref "R322") (pin "2") (pinfunction "2_2") (pintype "passive"))
      (node (ref "U59") (pin "5") (pinfunction "VTTSNS_5") (pintype "input"))
    )
    (net (code "237") (name "QDR01_VREF") (class "Default")
      (node (ref "C569") (pin "2") (pinfunction "2_2") (pintype "passive"))
      (node (ref "U57") (pin "H10") (pinfunction "VREF0_H10") (pintype "power_in"))
      (node (ref "U57") (pin "H2") (pinfunction "VREF1_H2") (pintype "power_in"))
      (node (ref "U58") (pin "H10") (pinfunction "VREF0_H10") (pintype "power_in"))
      (node (ref "U58") (pin "H2") (pinfunction "VREF1_H2") (pintype "power_in"))
      (node (ref "U59") (pin "6") (pinfunction "VTTREF_6") (pintype "output"))
    )
    (net (code "238") (name "QDR01_VTT") (class "Default")
      (node (ref "C553") (pin "2") (pinfunction "2_2") (pintype "passive"))
      (node (ref "C554") (pin "2") (pinfunction "2_2") (pintype "passive"))
      (node (ref "C555") (pin "2") (pinfunction "2_2") (pintype "passive"))
      (node (ref "C556") (pin "2") (pinfunction "2_2") (pintype "passive"))
      (node (ref "C557") (pin "2") (pinfunction "2_2") (pintype "passive"))
      (node (ref "C558") (pin "2") (pinfunction "2_2") (pintype "passive"))
      (node (ref "C560") (pin "2") (pinfunction "2_2") (pintype "passive"))
      (node (ref "C561") (pin "2") (pinfunction "2_2") (pintype "passive"))
      (node (ref "C562") (pin "2") (pinfunction "2_2") (pintype "passive"))
      (node (ref "C563") (pin "2") (pinfunction "2_2") (pintype "passive"))
      (node (ref "C564") (pin "2") (pinfunction "2_2") (pintype "passive"))
      (node (ref "C565") (pin "2") (pinfunction "2_2") (pintype "passive"))
      (node (ref "C570") (pin "2") (pinfunction "2_2") (pintype "passive"))
      (node (ref "C571") (pin "2") (pinfunction "2_2") (pintype "passive"))
      (node (ref "R114") (pin "2") (pinfunction "2_2") (pintype "passive"))
      (node (ref "R272") (pin "2") (pinfunction "2_2") (pintype "passive"))
      (node (ref "R274") (pin "2") (pinfunction "2_2") (pintype "passive"))
      (node (ref "R275") (pin "2") (pinfunction "2_2") (pintype "passive"))
      (node (ref "R276") (pin "2") (pinfunction "2_2") (pintype "passive"))
      (node (ref "R277") (pin "2") (pinfunction "2_2") (pintype "passive"))
      (node (ref "R322") (pin "1") (pinfunction "1_1") (pintype "passive"))
      (node (ref "RP10") (pin "5") (pinfunction "5_5") (pintype "passive"))
      (node (ref "RP10") (pin "6") (pinfunction "6_6") (pintype "passive"))
      (node (ref "RP10") (pin "7") (pinfunction "7_7") (pintype "passive"))
      (node (ref "RP10") (pin "8") (pinfunction "8_8") (pintype "passive"))
      (node (ref "RP11") (pin "5") (pinfunction "5_5") (pintype "passive"))
      (node (ref "RP11") (pin "6") (pinfunction "6_6") (pintype "passive"))
      (node (ref "RP11") (pin "7") (pinfunction "7_7") (pintype "passive"))
      (node (ref "RP11") (pin "8") (pinfunction "8_8") (pintype "passive"))
      (node (ref "RP12") (pin "5") (pinfunction "5_5") (pintype "passive"))
      (node (ref "RP12") (pin "6") (pinfunction "6_6") (pintype "passive"))
      (node (ref "RP12") (pin "7") (pinfunction "7_7") (pintype "passive"))
      (node (ref "RP12") (pin "8") (pinfunction "8_8") (pintype "passive"))
      (node (ref "RP13") (pin "5") (pinfunction "5_5") (pintype "passive"))
      (node (ref "RP13") (pin "6") (pinfunction "6_6") (pintype "passive"))
      (node (ref "RP13") (pin "7") (pinfunction "7_7") (pintype "passive"))
      (node (ref "RP13") (pin "8") (pinfunction "8_8") (pintype "passive"))
      (node (ref "RP14") (pin "5") (pinfunction "5_5") (pintype "passive"))
      (node (ref "RP14") (pin "6") (pinfunction "6_6") (pintype "passive"))
      (node (ref "RP14") (pin "7") (pinfunction "7_7") (pintype "passive"))
      (node (ref "RP14") (pin "8") (pinfunction "8_8") (pintype "passive"))
      (node (ref "RP15") (pin "5") (pinfunction "5_5") (pintype "passive"))
      (node (ref "RP15") (pin "6") (pinfunction "6_6") (pintype "passive"))
      (node (ref "RP15") (pin "7") (pinfunction "7_7") (pintype "passive"))
      (node (ref "RP15") (pin "8") (pinfunction "8_8") (pintype "passive"))
      (node (ref "RP16") (pin "5") (pinfunction "5_5") (pintype "passive"))
      (node (ref "RP16") (pin "6") (pinfunction "6_6") (pintype "passive"))
      (node (ref "RP16") (pin "7") (pinfunction "7_7") (pintype "passive"))
      (node (ref "RP16") (pin "8") (pinfunction "8_8") (pintype "passive"))
      (node (ref "RP7") (pin "5") (pinfunction "5_5") (pintype "passive"))
      (node (ref "RP7") (pin "6") (pinfunction "6_6") (pintype "passive"))
      (node (ref "RP7") (pin "7") (pinfunction "7_7") (pintype "passive"))
      (node (ref "RP7") (pin "8") (pinfunction "8_8") (pintype "passive"))
      (node (ref "RP8") (pin "5") (pinfunction "5_5") (pintype "passive"))
      (node (ref "RP8") (pin "6") (pinfunction "6_6") (pintype "passive"))
      (node (ref "RP8") (pin "7") (pinfunction "7_7") (pintype "passive"))
      (node (ref "RP8") (pin "8") (pinfunction "8_8") (pintype "passive"))
      (node (ref "RP9") (pin "5") (pinfunction "5_5") (pintype "passive"))
      (node (ref "RP9") (pin "6") (pinfunction "6_6") (pintype "passive"))
      (node (ref "RP9") (pin "7") (pinfunction "7_7") (pintype "passive"))
      (node (ref "RP9") (pin "8") (pinfunction "8_8") (pintype "passive"))
      (node (ref "U59") (pin "3") (pinfunction "VTT_3") (pintype "output"))
    )
    (net (code "239") (name "unconnected-(U57A-CQ#-PadA1)") (class "Default")
      (node (ref "U57") (pin "A1") (pinfunction "CQ#_A1") (pintype "output+no_connect"))
    )
    (net (code "240") (name "unconnected-(U57D-NC1-PadC6)") (class "Default")
      (node (ref "U57") (pin "C6") (pinfunction "NC1_C6") (pintype "passive+no_connect"))
    )
    (net (code "241") (name "unconnected-(U58A-CQ#-PadA1)") (class "Default")
      (node (ref "U58") (pin "A1") (pinfunction "CQ#_A1") (pintype "output+no_connect"))
    )
    (net (code "242") (name "unconnected-(U58D-NC1-PadC6)") (class "Default")
      (node (ref "U58") (pin "C6") (pinfunction "NC1_C6") (pintype "passive+no_connect"))
    )
  )
)
